# BB_DIO_Cape.net
KiCad netlist of a schematic drawn in EAGLE
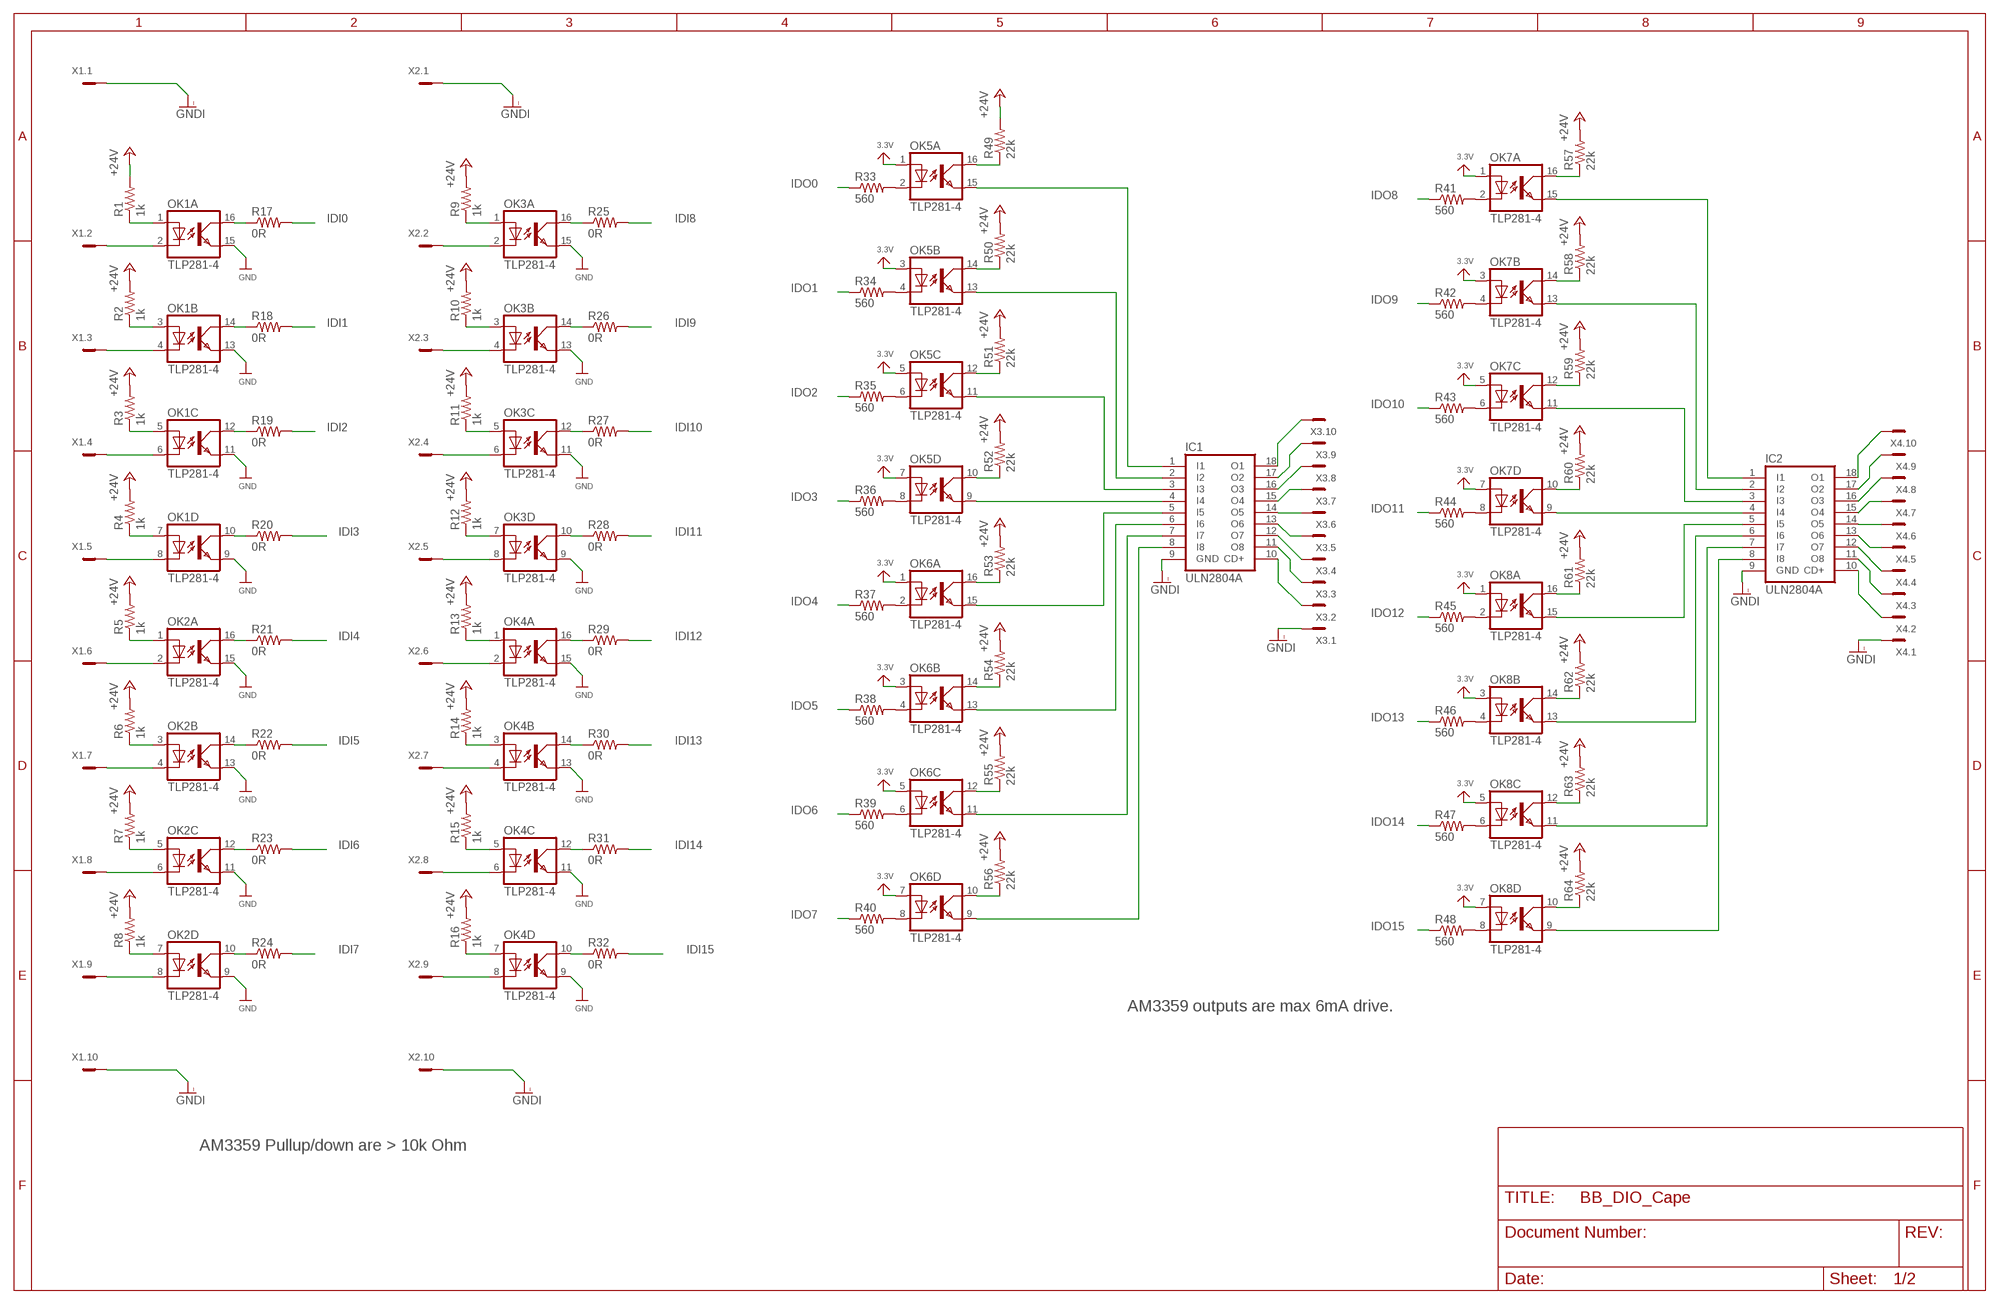
[diagram p0: schematic, sheet 1]
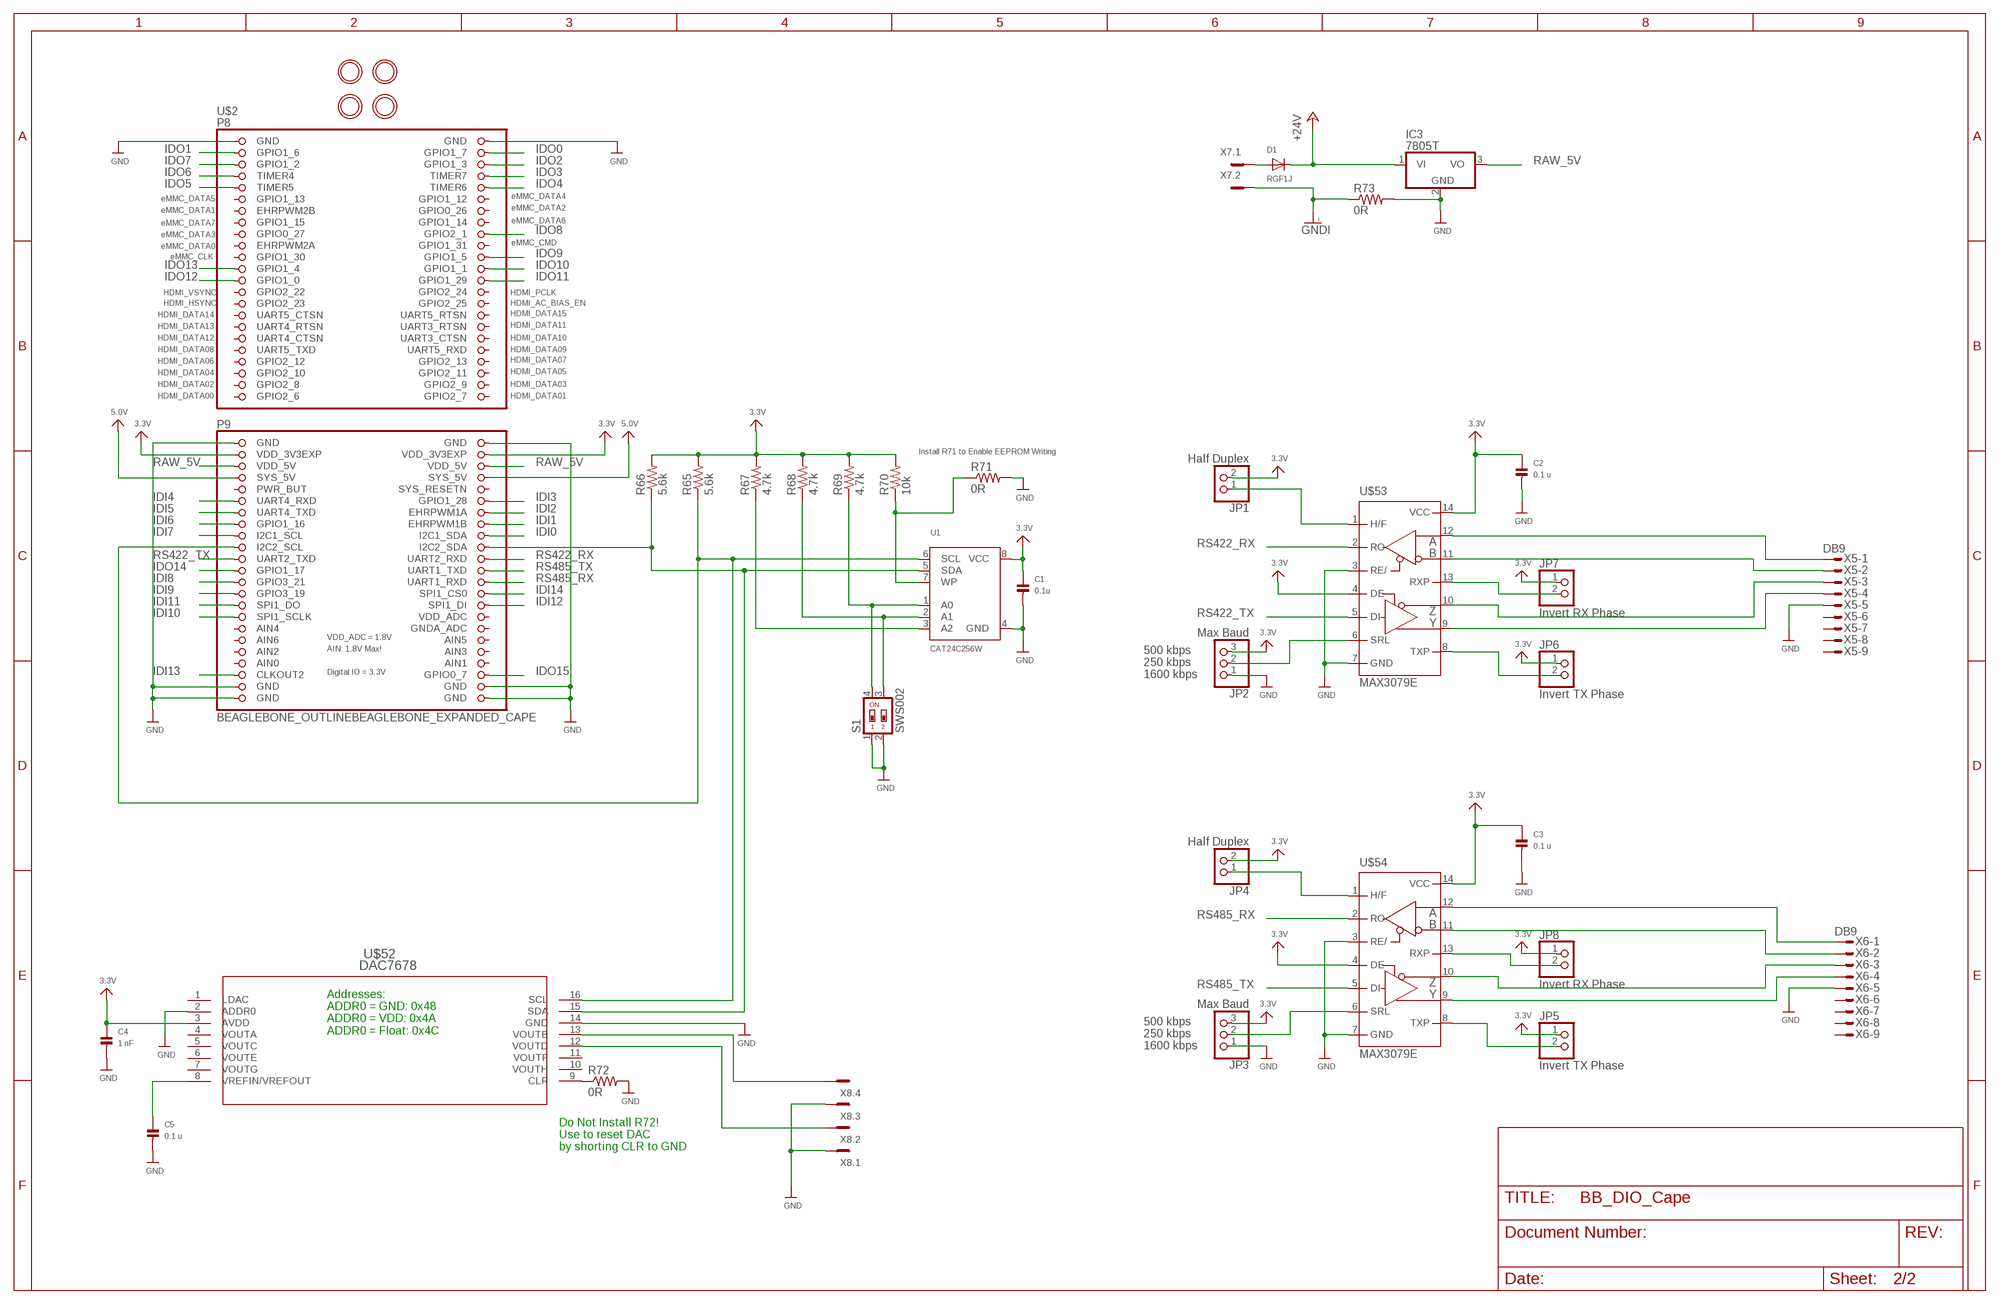
[diagram p1: schematic, sheet 2]

(export (version "E")
  (design (tool "Eeschema 10.0.6"))
  (components
    (comp (ref "IC1")
      (value "ULN2804A")
      (footprint "eagle-import:SO18W")
      (libsource (lib "eagle-import") (part "ULN2803ASOIC18"))
    )
    (comp (ref "IC2")
      (value "ULN2804A")
      (footprint "eagle-import:SO18W")
      (libsource (lib "eagle-import") (part "ULN2803ASOIC18"))
    )
    (comp (ref "OK1")
      (value "TLP281-4")
      (footprint "eagle-import:MINI-FLAT-16")
      (libsource (lib "eagle-import") (part "TLP283-4"))
    )
    (comp (ref "OK2")
      (value "TLP281-4")
      (footprint "eagle-import:MINI-FLAT-16")
      (libsource (lib "eagle-import") (part "TLP283-4"))
    )
    (comp (ref "OK3")
      (value "TLP281-4")
      (footprint "eagle-import:MINI-FLAT-16")
      (libsource (lib "eagle-import") (part "TLP283-4"))
    )
    (comp (ref "OK4")
      (value "TLP281-4")
      (footprint "eagle-import:MINI-FLAT-16")
      (libsource (lib "eagle-import") (part "TLP283-4"))
    )
    (comp (ref "OK5")
      (value "TLP281-4")
      (footprint "eagle-import:MINI-FLAT-16")
      (libsource (lib "eagle-import") (part "TLP283-4"))
    )
    (comp (ref "OK6")
      (value "TLP281-4")
      (footprint "eagle-import:MINI-FLAT-16")
      (libsource (lib "eagle-import") (part "TLP283-4"))
    )
    (comp (ref "OK7")
      (value "TLP281-4")
      (footprint "eagle-import:MINI-FLAT-16")
      (libsource (lib "eagle-import") (part "TLP283-4"))
    )
    (comp (ref "OK8")
      (value "TLP281-4")
      (footprint "eagle-import:MINI-FLAT-16")
      (libsource (lib "eagle-import") (part "TLP283-4"))
    )
    (comp (ref "R1")
      (value "1k")
      (footprint "eagle-import:R0603")
      (libsource (lib "eagle-import") (part "R-US_R0603"))
    )
    (comp (ref "R2")
      (value "1k")
      (footprint "eagle-import:R0603")
      (libsource (lib "eagle-import") (part "R-US_R0603"))
    )
    (comp (ref "R3")
      (value "1k")
      (footprint "eagle-import:R0603")
      (libsource (lib "eagle-import") (part "R-US_R0603"))
    )
    (comp (ref "R4")
      (value "1k")
      (footprint "eagle-import:R0603")
      (libsource (lib "eagle-import") (part "R-US_R0603"))
    )
    (comp (ref "R5")
      (value "1k")
      (footprint "eagle-import:R0603")
      (libsource (lib "eagle-import") (part "R-US_R0603"))
    )
    (comp (ref "R6")
      (value "1k")
      (footprint "eagle-import:R0603")
      (libsource (lib "eagle-import") (part "R-US_R0603"))
    )
    (comp (ref "R7")
      (value "1k")
      (footprint "eagle-import:R0603")
      (libsource (lib "eagle-import") (part "R-US_R0603"))
    )
    (comp (ref "R8")
      (value "1k")
      (footprint "eagle-import:R0603")
      (libsource (lib "eagle-import") (part "R-US_R0603"))
    )
    (comp (ref "R9")
      (value "1k")
      (footprint "eagle-import:R0603")
      (libsource (lib "eagle-import") (part "R-US_R0603"))
    )
    (comp (ref "R10")
      (value "1k")
      (footprint "eagle-import:R0603")
      (libsource (lib "eagle-import") (part "R-US_R0603"))
    )
    (comp (ref "R11")
      (value "1k")
      (footprint "eagle-import:R0603")
      (libsource (lib "eagle-import") (part "R-US_R0603"))
    )
    (comp (ref "R12")
      (value "1k")
      (footprint "eagle-import:R0603")
      (libsource (lib "eagle-import") (part "R-US_R0603"))
    )
    (comp (ref "R13")
      (value "1k")
      (footprint "eagle-import:R0603")
      (libsource (lib "eagle-import") (part "R-US_R0603"))
    )
    (comp (ref "R14")
      (value "1k")
      (footprint "eagle-import:R0603")
      (libsource (lib "eagle-import") (part "R-US_R0603"))
    )
    (comp (ref "R15")
      (value "1k")
      (footprint "eagle-import:R0603")
      (libsource (lib "eagle-import") (part "R-US_R0603"))
    )
    (comp (ref "R16")
      (value "1k")
      (footprint "eagle-import:R0603")
      (libsource (lib "eagle-import") (part "R-US_R0603"))
    )
    (comp (ref "R17")
      (value "0R")
      (footprint "eagle-import:R0603")
      (libsource (lib "eagle-import") (part "R-US_R0603"))
    )
    (comp (ref "R18")
      (value "0R")
      (footprint "eagle-import:R0603")
      (libsource (lib "eagle-import") (part "R-US_R0603"))
    )
    (comp (ref "R19")
      (value "0R")
      (footprint "eagle-import:R0603")
      (libsource (lib "eagle-import") (part "R-US_R0603"))
    )
    (comp (ref "R20")
      (value "0R")
      (footprint "eagle-import:R0603")
      (libsource (lib "eagle-import") (part "R-US_R0603"))
    )
    (comp (ref "R21")
      (value "0R")
      (footprint "eagle-import:R0603")
      (libsource (lib "eagle-import") (part "R-US_R0603"))
    )
    (comp (ref "R22")
      (value "0R")
      (footprint "eagle-import:R0603")
      (libsource (lib "eagle-import") (part "R-US_R0603"))
    )
    (comp (ref "R23")
      (value "0R")
      (footprint "eagle-import:R0603")
      (libsource (lib "eagle-import") (part "R-US_R0603"))
    )
    (comp (ref "R24")
      (value "0R")
      (footprint "eagle-import:R0603")
      (libsource (lib "eagle-import") (part "R-US_R0603"))
    )
    (comp (ref "R25")
      (value "0R")
      (footprint "eagle-import:R0603")
      (libsource (lib "eagle-import") (part "R-US_R0603"))
    )
    (comp (ref "R26")
      (value "0R")
      (footprint "eagle-import:R0603")
      (libsource (lib "eagle-import") (part "R-US_R0603"))
    )
    (comp (ref "R27")
      (value "0R")
      (footprint "eagle-import:R0603")
      (libsource (lib "eagle-import") (part "R-US_R0603"))
    )
    (comp (ref "R28")
      (value "0R")
      (footprint "eagle-import:R0603")
      (libsource (lib "eagle-import") (part "R-US_R0603"))
    )
    (comp (ref "R29")
      (value "0R")
      (footprint "eagle-import:R0603")
      (libsource (lib "eagle-import") (part "R-US_R0603"))
    )
    (comp (ref "R30")
      (value "0R")
      (footprint "eagle-import:R0603")
      (libsource (lib "eagle-import") (part "R-US_R0603"))
    )
    (comp (ref "R31")
      (value "0R")
      (footprint "eagle-import:R0603")
      (libsource (lib "eagle-import") (part "R-US_R0603"))
    )
    (comp (ref "R32")
      (value "0R")
      (footprint "eagle-import:R0603")
      (libsource (lib "eagle-import") (part "R-US_R0603"))
    )
    (comp (ref "R33")
      (value "560")
      (footprint "eagle-import:R0603")
      (libsource (lib "eagle-import") (part "R-US_R0603"))
    )
    (comp (ref "R34")
      (value "560")
      (footprint "eagle-import:R0603")
      (libsource (lib "eagle-import") (part "R-US_R0603"))
    )
    (comp (ref "R35")
      (value "560")
      (footprint "eagle-import:R0603")
      (libsource (lib "eagle-import") (part "R-US_R0603"))
    )
    (comp (ref "R36")
      (value "560")
      (footprint "eagle-import:R0603")
      (libsource (lib "eagle-import") (part "R-US_R0603"))
    )
    (comp (ref "R37")
      (value "560")
      (footprint "eagle-import:R0603")
      (libsource (lib "eagle-import") (part "R-US_R0603"))
    )
    (comp (ref "R38")
      (value "560")
      (footprint "eagle-import:R0603")
      (libsource (lib "eagle-import") (part "R-US_R0603"))
    )
    (comp (ref "R39")
      (value "560")
      (footprint "eagle-import:R0603")
      (libsource (lib "eagle-import") (part "R-US_R0603"))
    )
    (comp (ref "R40")
      (value "560")
      (footprint "eagle-import:R0603")
      (libsource (lib "eagle-import") (part "R-US_R0603"))
    )
    (comp (ref "R41")
      (value "560")
      (footprint "eagle-import:R0603")
      (libsource (lib "eagle-import") (part "R-US_R0603"))
    )
    (comp (ref "R42")
      (value "560")
      (footprint "eagle-import:R0603")
      (libsource (lib "eagle-import") (part "R-US_R0603"))
    )
    (comp (ref "R43")
      (value "560")
      (footprint "eagle-import:R0603")
      (libsource (lib "eagle-import") (part "R-US_R0603"))
    )
    (comp (ref "R44")
      (value "560")
      (footprint "eagle-import:R0603")
      (libsource (lib "eagle-import") (part "R-US_R0603"))
    )
    (comp (ref "R45")
      (value "560")
      (footprint "eagle-import:R0603")
      (libsource (lib "eagle-import") (part "R-US_R0603"))
    )
    (comp (ref "R46")
      (value "560")
      (footprint "eagle-import:R0603")
      (libsource (lib "eagle-import") (part "R-US_R0603"))
    )
    (comp (ref "R47")
      (value "560")
      (footprint "eagle-import:R0603")
      (libsource (lib "eagle-import") (part "R-US_R0603"))
    )
    (comp (ref "R48")
      (value "560")
      (footprint "eagle-import:R0603")
      (libsource (lib "eagle-import") (part "R-US_R0603"))
    )
    (comp (ref "R49")
      (value "22k")
      (footprint "eagle-import:R0603")
      (libsource (lib "eagle-import") (part "R-US_R0603"))
    )
    (comp (ref "R50")
      (value "22k")
      (footprint "eagle-import:R0603")
      (libsource (lib "eagle-import") (part "R-US_R0603"))
    )
    (comp (ref "R51")
      (value "22k")
      (footprint "eagle-import:R0603")
      (libsource (lib "eagle-import") (part "R-US_R0603"))
    )
    (comp (ref "R52")
      (value "22k")
      (footprint "eagle-import:R0603")
      (libsource (lib "eagle-import") (part "R-US_R0603"))
    )
    (comp (ref "R53")
      (value "22k")
      (footprint "eagle-import:R0603")
      (libsource (lib "eagle-import") (part "R-US_R0603"))
    )
    (comp (ref "R54")
      (value "22k")
      (footprint "eagle-import:R0603")
      (libsource (lib "eagle-import") (part "R-US_R0603"))
    )
    (comp (ref "R55")
      (value "22k")
      (footprint "eagle-import:R0603")
      (libsource (lib "eagle-import") (part "R-US_R0603"))
    )
    (comp (ref "R56")
      (value "22k")
      (footprint "eagle-import:R0603")
      (libsource (lib "eagle-import") (part "R-US_R0603"))
    )
    (comp (ref "R57")
      (value "22k")
      (footprint "eagle-import:R0603")
      (libsource (lib "eagle-import") (part "R-US_R0603"))
    )
    (comp (ref "R58")
      (value "22k")
      (footprint "eagle-import:R0603")
      (libsource (lib "eagle-import") (part "R-US_R0603"))
    )
    (comp (ref "R59")
      (value "22k")
      (footprint "eagle-import:R0603")
      (libsource (lib "eagle-import") (part "R-US_R0603"))
    )
    (comp (ref "R60")
      (value "22k")
      (footprint "eagle-import:R0603")
      (libsource (lib "eagle-import") (part "R-US_R0603"))
    )
    (comp (ref "R61")
      (value "22k")
      (footprint "eagle-import:R0603")
      (libsource (lib "eagle-import") (part "R-US_R0603"))
    )
    (comp (ref "R62")
      (value "22k")
      (footprint "eagle-import:R0603")
      (libsource (lib "eagle-import") (part "R-US_R0603"))
    )
    (comp (ref "R63")
      (value "22k")
      (footprint "eagle-import:R0603")
      (libsource (lib "eagle-import") (part "R-US_R0603"))
    )
    (comp (ref "R64")
      (value "22k")
      (footprint "eagle-import:R0603")
      (libsource (lib "eagle-import") (part "R-US_R0603"))
    )
    (comp (ref "X1")
      (value "MC10")
      (footprint "eagle-import:MC10")
      (libsource (lib "eagle-import") (part "MC10"))
    )
    (comp (ref "X2")
      (value "MC10")
      (footprint "eagle-import:MC10")
      (libsource (lib "eagle-import") (part "MC10"))
    )
    (comp (ref "X3")
      (value "MC10")
      (footprint "eagle-import:MC10")
      (libsource (lib "eagle-import") (part "MC10"))
    )
    (comp (ref "X4")
      (value "MC10")
      (footprint "eagle-import:MC10")
      (libsource (lib "eagle-import") (part "MC10"))
    )
    (comp (ref "C1")
      (value "0.1u")
      (footprint "eagle-import:_0603")
      (libsource (lib "eagle-import") (part "CAP_CERAMIC_0603"))
    )
    (comp (ref "C2")
      (value "0.1 u")
      (footprint "eagle-import:0603")
      (libsource (lib "eagle-import") (part "CAP_CERAMIC0603"))
    )
    (comp (ref "C3")
      (value "0.1 u")
      (footprint "eagle-import:0603")
      (libsource (lib "eagle-import") (part "CAP_CERAMIC0603"))
    )
    (comp (ref "C4")
      (value "1 nF")
      (footprint "eagle-import:0603")
      (libsource (lib "eagle-import") (part "CAP_CERAMIC0603"))
    )
    (comp (ref "C5")
      (value "0.1 u")
      (footprint "eagle-import:0603")
      (libsource (lib "eagle-import") (part "CAP_CERAMIC0603"))
    )
    (comp (ref "D1")
      (value "RGF1J")
      (footprint "eagle-import:SMADIODE")
      (libsource (lib "eagle-import") (part "DIODESMA"))
    )
    (comp (ref "IC3")
      (value "7805T")
      (footprint "eagle-import:TO220H")
      (libsource (lib "eagle-import") (part "78T05"))
    )
    (comp (ref "JP1")
      (value "Half Duplex")
      (footprint "eagle-import:1X02_ROUND")
      (libsource (lib "eagle-import") (part "HEADER-1X2ROUND"))
    )
    (comp (ref "JP2")
      (value "Max Baud")
      (footprint "eagle-import:1X03_ROUND")
      (libsource (lib "eagle-import") (part "HEADER-1X3ROUND"))
    )
    (comp (ref "JP3")
      (value "Max Baud")
      (footprint "eagle-import:1X03_ROUND")
      (libsource (lib "eagle-import") (part "HEADER-1X3ROUND"))
    )
    (comp (ref "JP4")
      (value "Half Duplex")
      (footprint "eagle-import:1X02_ROUND")
      (libsource (lib "eagle-import") (part "HEADER-1X2ROUND"))
    )
    (comp (ref "JP5")
      (value "Invert TX Phase")
      (footprint "eagle-import:1X02_ROUND")
      (libsource (lib "eagle-import") (part "HEADER-1X2ROUND"))
    )
    (comp (ref "JP6")
      (value "Invert TX Phase")
      (footprint "eagle-import:1X02_ROUND")
      (libsource (lib "eagle-import") (part "HEADER-1X2ROUND"))
    )
    (comp (ref "JP7")
      (value "Invert RX Phase")
      (footprint "eagle-import:1X02_ROUND")
      (libsource (lib "eagle-import") (part "HEADER-1X2ROUND"))
    )
    (comp (ref "JP8")
      (value "Invert RX Phase")
      (footprint "eagle-import:1X02_ROUND")
      (libsource (lib "eagle-import") (part "HEADER-1X2ROUND"))
    )
    (comp (ref "R65")
      (value "5.6k")
      (footprint "eagle-import:R0603")
      (libsource (lib "eagle-import") (part "R-US_R0603"))
    )
    (comp (ref "R66")
      (value "5.6k")
      (footprint "eagle-import:R0603")
      (libsource (lib "eagle-import") (part "R-US_R0603"))
    )
    (comp (ref "R67")
      (value "4.7k")
      (footprint "eagle-import:R0603")
      (libsource (lib "eagle-import") (part "R-US_R0603"))
    )
    (comp (ref "R68")
      (value "4.7k")
      (footprint "eagle-import:R0603")
      (libsource (lib "eagle-import") (part "R-US_R0603"))
    )
    (comp (ref "R69")
      (value "4.7k")
      (footprint "eagle-import:R0603")
      (libsource (lib "eagle-import") (part "R-US_R0603"))
    )
    (comp (ref "R70")
      (value "10k")
      (footprint "eagle-import:R0603")
      (libsource (lib "eagle-import") (part "R-US_R0603"))
    )
    (comp (ref "R71")
      (value "0R")
      (footprint "eagle-import:R0603")
      (libsource (lib "eagle-import") (part "R-US_R0603"))
    )
    (comp (ref "R72")
      (value "0R")
      (footprint "eagle-import:R0603")
      (libsource (lib "eagle-import") (part "R-US_R0603"))
    )
    (comp (ref "R73")
      (value "0R")
      (footprint "eagle-import:M1206")
      (libsource (lib "eagle-import") (part "R-US_M1206"))
    )
    (comp (ref "S1")
      (value "SWS002")
      (footprint "eagle-import:SMS-002")
      (libsource (lib "eagle-import") (part "SWS002"))
    )
    (comp (ref "U$2")
      (value "BEAGLEBONE_OUTLINEBEAGLEBONE_EXPANDED_CAPE")
      (footprint "eagle-import:BEAGLEBONE_SHIELD")
      (libsource (lib "eagle-import") (part "BEAGLEBONE_OUTLINEBEAGLEBONE_EXPANDED_CAPE"))
    )
    (comp (ref "U$22")
      (value "MOUNTINGHOLE3.0THIN")
      (footprint "eagle-import:MOUNTINGHOLE_3.0_PLATEDTHIN")
      (libsource (lib "eagle-import") (part "MOUNTINGHOLE3.0THIN"))
    )
    (comp (ref "U$23")
      (value "MOUNTINGHOLE3.0THIN")
      (footprint "eagle-import:MOUNTINGHOLE_3.0_PLATEDTHIN")
      (libsource (lib "eagle-import") (part "MOUNTINGHOLE3.0THIN"))
    )
    (comp (ref "U$52")
      (value "DAC7678")
      (footprint "eagle-import:PW16")
      (libsource (lib "eagle-import") (part "DAC7678"))
    )
    (comp (ref "U$53")
      (value "MAX3079E")
      (footprint "eagle-import:SO14")
      (libsource (lib "eagle-import") (part "MAX3079E"))
    )
    (comp (ref "U$54")
      (value "MAX3079E")
      (footprint "eagle-import:SO14")
      (libsource (lib "eagle-import") (part "MAX3079E"))
    )
    (comp (ref "U$71")
      (value "MOUNTINGHOLE3.0THIN")
      (footprint "eagle-import:MOUNTINGHOLE_3.0_PLATEDTHIN")
      (libsource (lib "eagle-import") (part "MOUNTINGHOLE3.0THIN"))
    )
    (comp (ref "U$72")
      (value "MOUNTINGHOLE3.0THIN")
      (footprint "eagle-import:MOUNTINGHOLE_3.0_PLATEDTHIN")
      (libsource (lib "eagle-import") (part "MOUNTINGHOLE3.0THIN"))
    )
    (comp (ref "U1")
      (value "CAT24C256W")
      (footprint "eagle-import:SOIC8_150MIL")
      (libsource (lib "eagle-import") (part "EEPROM_I2C_SOIC8_GENERIC"))
    )
    (comp (ref "X5")
      (value "DB9")
      (footprint "eagle-import:182-009-MALE")
      (libsource (lib "eagle-import") (part "M09?S-182"))
    )
    (comp (ref "X6")
      (value "DB9")
      (footprint "eagle-import:182-009-MALE")
      (libsource (lib "eagle-import") (part "M09?S-182"))
    )
    (comp (ref "X7")
      (value "MC2")
      (footprint "eagle-import:MC2")
      (libsource (lib "eagle-import") (part "MC2"))
    )
    (comp (ref "X8")
      (value "MC4")
      (footprint "eagle-import:MC4")
      (libsource (lib "eagle-import") (part "MC4"))
    )
  )
  (nets
    (net (code "1") (name "+24V") (class "Default")
      (node (ref "D1") (pin "C") (pinfunction "C_C") (pintype "passive"))
      (node (ref "IC3") (pin "1") (pinfunction "VI_1") (pintype "input"))
      (node (ref "R1") (pin "2") (pinfunction "2_2") (pintype "passive"))
      (node (ref "R10") (pin "2") (pinfunction "2_2") (pintype "passive"))
      (node (ref "R11") (pin "2") (pinfunction "2_2") (pintype "passive"))
      (node (ref "R12") (pin "2") (pinfunction "2_2") (pintype "passive"))
      (node (ref "R13") (pin "2") (pinfunction "2_2") (pintype "passive"))
      (node (ref "R14") (pin "2") (pinfunction "2_2") (pintype "passive"))
      (node (ref "R15") (pin "2") (pinfunction "2_2") (pintype "passive"))
      (node (ref "R16") (pin "2") (pinfunction "2_2") (pintype "passive"))
      (node (ref "R2") (pin "2") (pinfunction "2_2") (pintype "passive"))
      (node (ref "R3") (pin "2") (pinfunction "2_2") (pintype "passive"))
      (node (ref "R4") (pin "2") (pinfunction "2_2") (pintype "passive"))
      (node (ref "R49") (pin "2") (pinfunction "2_2") (pintype "passive"))
      (node (ref "R5") (pin "2") (pinfunction "2_2") (pintype "passive"))
      (node (ref "R50") (pin "2") (pinfunction "2_2") (pintype "passive"))
      (node (ref "R51") (pin "2") (pinfunction "2_2") (pintype "passive"))
      (node (ref "R52") (pin "2") (pinfunction "2_2") (pintype "passive"))
      (node (ref "R53") (pin "2") (pinfunction "2_2") (pintype "passive"))
      (node (ref "R54") (pin "2") (pinfunction "2_2") (pintype "passive"))
      (node (ref "R55") (pin "2") (pinfunction "2_2") (pintype "passive"))
      (node (ref "R56") (pin "2") (pinfunction "2_2") (pintype "passive"))
      (node (ref "R57") (pin "2") (pinfunction "2_2") (pintype "passive"))
      (node (ref "R58") (pin "2") (pinfunction "2_2") (pintype "passive"))
      (node (ref "R59") (pin "2") (pinfunction "2_2") (pintype "passive"))
      (node (ref "R6") (pin "2") (pinfunction "2_2") (pintype "passive"))
      (node (ref "R60") (pin "2") (pinfunction "2_2") (pintype "passive"))
      (node (ref "R61") (pin "2") (pinfunction "2_2") (pintype "passive"))
      (node (ref "R62") (pin "2") (pinfunction "2_2") (pintype "passive"))
      (node (ref "R63") (pin "2") (pinfunction "2_2") (pintype "passive"))
      (node (ref "R64") (pin "2") (pinfunction "2_2") (pintype "passive"))
      (node (ref "R7") (pin "2") (pinfunction "2_2") (pintype "passive"))
      (node (ref "R8") (pin "2") (pinfunction "2_2") (pintype "passive"))
      (node (ref "R9") (pin "2") (pinfunction "2_2") (pintype "passive"))
    )
    (net (code "2") (name "3.3V") (class "Default")
      (node (ref "C1") (pin "1") (pinfunction "P$1_1") (pintype "passive"))
      (node (ref "C2") (pin "1") (pinfunction "P$1_1") (pintype "passive"))
      (node (ref "C3") (pin "1") (pinfunction "P$1_1") (pintype "passive"))
      (node (ref "C4") (pin "1") (pinfunction "P$1_1") (pintype "passive"))
      (node (ref "JP1") (pin "2") (pinfunction "2_2") (pintype "passive"))
      (node (ref "JP2") (pin "3") (pinfunction "3_3") (pintype "passive"))
      (node (ref "JP3") (pin "3") (pinfunction "3_3") (pintype "passive"))
      (node (ref "JP4") (pin "2") (pinfunction "2_2") (pintype "passive"))
      (node (ref "JP5") (pin "1") (pinfunction "1_1") (pintype "passive"))
      (node (ref "JP6") (pin "1") (pinfunction "1_1") (pintype "passive"))
      (node (ref "JP7") (pin "1") (pinfunction "1_1") (pintype "passive"))
      (node (ref "JP8") (pin "1") (pinfunction "1_1") (pintype "passive"))
      (node (ref "OK5") (pin "1") (pinfunction "A_1") (pintype "passive"))
      (node (ref "OK5") (pin "3") (pinfunction "A_3") (pintype "passive"))
      (node (ref "OK5") (pin "5") (pinfunction "A_5") (pintype "passive"))
      (node (ref "OK5") (pin "7") (pinfunction "A_7") (pintype "passive"))
      (node (ref "OK6") (pin "1") (pinfunction "A_1") (pintype "passive"))
      (node (ref "OK6") (pin "3") (pinfunction "A_3") (pintype "passive"))
      (node (ref "OK6") (pin "5") (pinfunction "A_5") (pintype "passive"))
      (node (ref "OK6") (pin "7") (pinfunction "A_7") (pintype "passive"))
      (node (ref "OK7") (pin "1") (pinfunction "A_1") (pintype "passive"))
      (node (ref "OK7") (pin "3") (pinfunction "A_3") (pintype "passive"))
      (node (ref "OK7") (pin "5") (pinfunction "A_5") (pintype "passive"))
      (node (ref "OK7") (pin "7") (pinfunction "A_7") (pintype "passive"))
      (node (ref "OK8") (pin "1") (pinfunction "A_1") (pintype "passive"))
      (node (ref "OK8") (pin "3") (pinfunction "A_3") (pintype "passive"))
      (node (ref "OK8") (pin "5") (pinfunction "A_5") (pintype "passive"))
      (node (ref "OK8") (pin "7") (pinfunction "A_7") (pintype "passive"))
      (node (ref "R65") (pin "2") (pinfunction "2_2") (pintype "passive"))
      (node (ref "R66") (pin "2") (pinfunction "2_2") (pintype "passive"))
      (node (ref "R67") (pin "2") (pinfunction "2_2") (pintype "passive"))
      (node (ref "R68") (pin "2") (pinfunction "2_2") (pintype "passive"))
      (node (ref "R69") (pin "2") (pinfunction "2_2") (pintype "passive"))
      (node (ref "R70") (pin "2") (pinfunction "2_2") (pintype "passive"))
      (node (ref "U$2") (pin "49") (pinfunction "VDD_3V3EXP_49") (pintype "power_in"))
      (node (ref "U$2") (pin "50") (pinfunction "VDD_3V3EXP_50") (pintype "power_in"))
      (node (ref "U$52") (pin "3") (pinfunction "AVDD_3") (pintype "power_in"))
      (node (ref "U$53") (pin "14") (pinfunction "VCC_14") (pintype "input"))
      (node (ref "U$53") (pin "4") (pinfunction "DE_4") (pintype "input"))
      (node (ref "U$54") (pin "14") (pinfunction "VCC_14") (pintype "input"))
      (node (ref "U$54") (pin "4") (pinfunction "DE_4") (pintype "input"))
      (node (ref "U1") (pin "8") (pinfunction "VCC_8") (pintype "power_in"))
    )
    (net (code "3") (name "5.0V") (class "Default")
      (node (ref "U$2") (pin "53") (pinfunction "SYS_5V_53") (pintype "power_in"))
      (node (ref "U$2") (pin "54") (pinfunction "SYS_5V_54") (pintype "power_in"))
    )
    (net (code "4") (name "GND") (class "Default")
      (node (ref "C1") (pin "2") (pinfunction "P$2_2") (pintype "passive"))
      (node (ref "C2") (pin "2") (pinfunction "P$2_2") (pintype "passive"))
      (node (ref "C3") (pin "2") (pinfunction "P$2_2") (pintype "passive"))
      (node (ref "C4") (pin "2") (pinfunction "P$2_2") (pintype "passive"))
      (node (ref "C5") (pin "2") (pinfunction "P$2_2") (pintype "passive"))
      (node (ref "IC3") (pin "2") (pinfunction "GND_2") (pintype "passive"))
      (node (ref "JP2") (pin "1") (pinfunction "1_1") (pintype "passive"))
      (node (ref "JP3") (pin "1") (pinfunction "1_1") (pintype "passive"))
      (node (ref "OK1") (pin "11") (pinfunction "EMIT_11") (pintype "passive"))
      (node (ref "OK1") (pin "13") (pinfunction "EMIT_13") (pintype "passive"))
      (node (ref "OK1") (pin "15") (pinfunction "EMIT_15") (pintype "passive"))
      (node (ref "OK1") (pin "9") (pinfunction "EMIT_9") (pintype "passive"))
      (node (ref "OK2") (pin "11") (pinfunction "EMIT_11") (pintype "passive"))
      (node (ref "OK2") (pin "13") (pinfunction "EMIT_13") (pintype "passive"))
      (node (ref "OK2") (pin "15") (pinfunction "EMIT_15") (pintype "passive"))
      (node (ref "OK2") (pin "9") (pinfunction "EMIT_9") (pintype "passive"))
      (node (ref "OK3") (pin "11") (pinfunction "EMIT_11") (pintype "passive"))
      (node (ref "OK3") (pin "13") (pinfunction "EMIT_13") (pintype "passive"))
      (node (ref "OK3") (pin "15") (pinfunction "EMIT_15") (pintype "passive"))
      (node (ref "OK3") (pin "9") (pinfunction "EMIT_9") (pintype "passive"))
      (node (ref "OK4") (pin "11") (pinfunction "EMIT_11") (pintype "passive"))
      (node (ref "OK4") (pin "13") (pinfunction "EMIT_13") (pintype "passive"))
      (node (ref "OK4") (pin "15") (pinfunction "EMIT_15") (pintype "passive"))
      (node (ref "OK4") (pin "9") (pinfunction "EMIT_9") (pintype "passive"))
      (node (ref "R71") (pin "2") (pinfunction "2_2") (pintype "passive"))
      (node (ref "R72") (pin "2") (pinfunction "2_2") (pintype "passive"))
      (node (ref "R73") (pin "2") (pinfunction "2_2") (pintype "passive"))
      (node (ref "S1") (pin "1") (pinfunction "1_1") (pintype "passive"))
      (node (ref "S1") (pin "2") (pinfunction "2_2") (pintype "passive"))
      (node (ref "U$2") (pin "1") (pinfunction "GND_1") (pintype "power_in"))
      (node (ref "U$2") (pin "2") (pinfunction "GND_2") (pintype "power_in"))
      (node (ref "U$2") (pin "47") (pinfunction "GND_47") (pintype "power_in"))
      (node (ref "U$2") (pin "48") (pinfunction "GND_48") (pintype "power_in"))
      (node (ref "U$2") (pin "89") (pinfunction "GND_89") (pintype "power_in"))
      (node (ref "U$2") (pin "90") (pinfunction "GND_90") (pintype "power_in"))
      (node (ref "U$2") (pin "91") (pinfunction "GND_91") (pintype "power_in"))
      (node (ref "U$2") (pin "92") (pinfunction "GND_92") (pintype "power_in"))
      (node (ref "U$52") (pin "14") (pinfunction "GND_14") (pintype "power_in"))
      (node (ref "U$52") (pin "2") (pinfunction "ADDR0_2") (pintype "input"))
      (node (ref "U$53") (pin "3") (pinfunction "RE/_3") (pintype "input"))
      (node (ref "U$53") (pin "7") (pinfunction "GND_7") (pintype "input"))
      (node (ref "U$54") (pin "3") (pinfunction "RE/_3") (pintype "input"))
      (node (ref "U$54") (pin "7") (pinfunction "GND_7") (pintype "input"))
      (node (ref "U1") (pin "4") (pinfunction "GND_4") (pintype "power_in"))
      (node (ref "X5") (pin "5") (pinfunction "M_5") (pintype "passive"))
      (node (ref "X6") (pin "5") (pinfunction "M_5") (pintype "passive"))
      (node (ref "X8") (pin "1") (pinfunction "SK_1") (pintype "passive"))
      (node (ref "X8") (pin "3") (pinfunction "SK_3") (pintype "passive"))
    )
    (net (code "5") (name "GNDA_ADC") (class "Default")
      (node (ref "U$2") (pin "80") (pinfunction "GNDA_ADC_80") (pintype "power_in"))
    )
    (net (code "6") (name "GNDI") (class "Default")
      (node (ref "IC1") (pin "9") (pinfunction "GND_9") (pintype "power_in"))
      (node (ref "IC2") (pin "9") (pinfunction "GND_9") (pintype "power_in"))
      (node (ref "R73") (pin "1") (pinfunction "1_1") (pintype "passive"))
      (node (ref "X1") (pin "1") (pinfunction "SK_1") (pintype "passive"))
      (node (ref "X1") (pin "10") (pinfunction "SK_10") (pintype "passive"))
      (node (ref "X2") (pin "1") (pinfunction "SK_1") (pintype "passive"))
      (node (ref "X2") (pin "10") (pinfunction "SK_10") (pintype "passive"))
      (node (ref "X3") (pin "1") (pinfunction "SK_1") (pintype "passive"))
      (node (ref "X4") (pin "1") (pinfunction "SK_1") (pintype "passive"))
      (node (ref "X7") (pin "2") (pinfunction "SK_2") (pintype "passive"))
    )
    (net (code "7") (name "IDI0") (class "Default")
      (node (ref "R17") (pin "2") (pinfunction "2_2") (pintype "passive"))
      (node (ref "U$2") (pin "64") (pinfunction "I2C1_SDA_64") (pintype "bidirectional"))
    )
    (net (code "8") (name "IDI1") (class "Default")
      (node (ref "R18") (pin "2") (pinfunction "2_2") (pintype "passive"))
      (node (ref "U$2") (pin "62") (pinfunction "EHRPWM1B_62") (pintype "bidirectional"))
    )
    (net (code "9") (name "IDI2") (class "Default")
      (node (ref "R19") (pin "2") (pinfunction "2_2") (pintype "passive"))
      (node (ref "U$2") (pin "60") (pinfunction "EHRPWM1A_60") (pintype "bidirectional"))
    )
    (net (code "10") (name "IDI3") (class "Default")
      (node (ref "R20") (pin "2") (pinfunction "2_2") (pintype "passive"))
      (node (ref "U$2") (pin "58") (pinfunction "GPIO1_28_58") (pintype "bidirectional"))
    )
    (net (code "11") (name "IDI4") (class "Default")
      (node (ref "R21") (pin "2") (pinfunction "2_2") (pintype "passive"))
      (node (ref "U$2") (pin "57") (pinfunction "UART4_RXD_57") (pintype "input"))
    )
    (net (code "12") (name "IDI5") (class "Default")
      (node (ref "R22") (pin "2") (pinfunction "2_2") (pintype "passive"))
      (node (ref "U$2") (pin "59") (pinfunction "UART4_TXD_59") (pintype "output"))
    )
    (net (code "13") (name "IDI6") (class "Default")
      (node (ref "R23") (pin "2") (pinfunction "2_2") (pintype "passive"))
      (node (ref "U$2") (pin "61") (pinfunction "GPIO1_16_61") (pintype "bidirectional"))
    )
    (net (code "14") (name "IDI7") (class "Default")
      (node (ref "R24") (pin "2") (pinfunction "2_2") (pintype "passive"))
      (node (ref "U$2") (pin "63") (pinfunction "I2C1_SCL_63") (pintype "bidirectional"))
    )
    (net (code "15") (name "IDI8") (class "Default")
      (node (ref "R25") (pin "2") (pinfunction "2_2") (pintype "passive"))
      (node (ref "U$2") (pin "71") (pinfunction "GPIO3_21_71") (pintype "bidirectional"))
    )
    (net (code "16") (name "IDI9") (class "Default")
      (node (ref "R26") (pin "2") (pinfunction "2_2") (pintype "passive"))
      (node (ref "U$2") (pin "73") (pinfunction "GPIO3_19_73") (pintype "bidirectional"))
    )
    (net (code "17") (name "IDI10") (class "Default")
      (node (ref "R27") (pin "2") (pinfunction "2_2") (pintype "passive"))
      (node (ref "U$2") (pin "77") (pinfunction "SPI1_SCLK_77") (pintype "bidirectional"))
    )
    (net (code "18") (name "IDI11") (class "Default")
      (node (ref "R28") (pin "2") (pinfunction "2_2") (pintype "passive"))
      (node (ref "U$2") (pin "75") (pinfunction "SPI1_DO_75") (pintype "bidirectional"))
    )
    (net (code "19") (name "IDI12") (class "Default")
      (node (ref "R29") (pin "2") (pinfunction "2_2") (pintype "passive"))
      (node (ref "U$2") (pin "76") (pinfunction "SPI1_DI_76") (pintype "bidirectional"))
    )
    (net (code "20") (name "IDI13") (class "Default")
      (node (ref "R30") (pin "2") (pinfunction "2_2") (pintype "passive"))
      (node (ref "U$2") (pin "87") (pinfunction "CLKOUT2_87") (pintype "output"))
    )
    (net (code "21") (name "IDI14") (class "Default")
      (node (ref "R31") (pin "2") (pinfunction "2_2") (pintype "passive"))
      (node (ref "U$2") (pin "74") (pinfunction "SPI1_CS0_74") (pintype "bidirectional"))
    )
    (net (code "22") (name "IDI15") (class "Default")
      (node (ref "R32") (pin "2") (pinfunction "2_2") (pintype "passive"))
    )
    (net (code "23") (name "IDO0") (class "Default")
      (node (ref "R33") (pin "1") (pinfunction "1_1") (pintype "passive"))
      (node (ref "U$2") (pin "4") (pinfunction "GPIO1_7_4") (pintype "bidirectional"))
    )
    (net (code "24") (name "IDO1") (class "Default")
      (node (ref "R34") (pin "1") (pinfunction "1_1") (pintype "passive"))
      (node (ref "U$2") (pin "3") (pinfunction "GPIO1_6_3") (pintype "bidirectional"))
    )
    (net (code "25") (name "IDO2") (class "Default")
      (node (ref "R35") (pin "1") (pinfunction "1_1") (pintype "passive"))
      (node (ref "U$2") (pin "6") (pinfunction "GPIO1_3_6") (pintype "bidirectional"))
    )
    (net (code "26") (name "IDO3") (class "Default")
      (node (ref "R36") (pin "1") (pinfunction "1_1") (pintype "passive"))
      (node (ref "U$2") (pin "8") (pinfunction "TIMER7_8") (pintype "bidirectional"))
    )
    (net (code "27") (name "IDO4") (class "Default")
      (node (ref "R37") (pin "1") (pinfunction "1_1") (pintype "passive"))
      (node (ref "U$2") (pin "10") (pinfunction "TIMER6_10") (pintype "bidirectional"))
    )
    (net (code "28") (name "IDO5") (class "Default")
      (node (ref "R38") (pin "1") (pinfunction "1_1") (pintype "passive"))
      (node (ref "U$2") (pin "9") (pinfunction "TIMER5_9") (pintype "bidirectional"))
    )
    (net (code "29") (name "IDO6") (class "Default")
      (node (ref "R39") (pin "1") (pinfunction "1_1") (pintype "passive"))
      (node (ref "U$2") (pin "7") (pinfunction "TIMER4_7") (pintype "bidirectional"))
    )
    (net (code "30") (name "IDO7") (class "Default")
      (node (ref "R40") (pin "1") (pinfunction "1_1") (pintype "passive"))
      (node (ref "U$2") (pin "5") (pinfunction "GPIO1_2_5") (pintype "bidirectional"))
    )
    (net (code "31") (name "IDO8") (class "Default")
      (node (ref "R41") (pin "1") (pinfunction "1_1") (pintype "passive"))
      (node (ref "U$2") (pin "18") (pinfunction "GPIO2_1_18") (pintype "bidirectional"))
    )
    (net (code "32") (name "IDO9") (class "Default")
      (node (ref "R42") (pin "1") (pinfunction "1_1") (pintype "passive"))
      (node (ref "U$2") (pin "22") (pinfunction "GPIO1_5_22") (pintype "bidirectional"))
    )
    (net (code "33") (name "IDO10") (class "Default")
      (node (ref "R43") (pin "1") (pinfunction "1_1") (pintype "passive"))
      (node (ref "U$2") (pin "24") (pinfunction "GPIO1_1_24") (pintype "bidirectional"))
    )
    (net (code "34") (name "IDO11") (class "Default")
      (node (ref "R44") (pin "1") (pinfunction "1_1") (pintype "passive"))
      (node (ref "U$2") (pin "26") (pinfunction "GPIO1_29_26") (pintype "bidirectional"))
    )
    (net (code "35") (name "IDO12") (class "Default")
      (node (ref "R45") (pin "1") (pinfunction "1_1") (pintype "passive"))
      (node (ref "U$2") (pin "25") (pinfunction "GPIO1_0_25") (pintype "bidirectional"))
    )
    (net (code "36") (name "IDO13") (class "Default")
      (node (ref "R46") (pin "1") (pinfunction "1_1") (pintype "passive"))
      (node (ref "U$2") (pin "23") (pinfunction "GPIO1_4_23") (pintype "bidirectional"))
    )
    (net (code "37") (name "IDO14") (class "Default")
      (node (ref "R47") (pin "1") (pinfunction "1_1") (pintype "passive"))
      (node (ref "U$2") (pin "69") (pinfunction "GPIO1_17_69") (pintype "bidirectional"))
    )
    (net (code "38") (name "IDO15") (class "Default")
      (node (ref "R48") (pin "1") (pinfunction "1_1") (pintype "passive"))
      (node (ref "U$2") (pin "88") (pinfunction "GPIO0_7_88") (pintype "bidirectional"))
    )
    (net (code "39") (name "Net-(C5-P$1)") (class "Default")
      (node (ref "C5") (pin "1") (pinfunction "P$1_1") (pintype "passive"))
      (node (ref "U$52") (pin "8") (pinfunction "VREFIN/VREFOUT_8") (pintype "bidirectional"))
    )
    (net (code "40") (name "Net-(IC1-CD+)") (class "Default")
      (node (ref "IC1") (pin "10") (pinfunction "CD+_10") (pintype "passive"))
      (node (ref "X3") (pin "2") (pinfunction "SK_2") (pintype "passive"))
    )
    (net (code "41") (name "Net-(IC1-I1)") (class "Default")
      (node (ref "IC1") (pin "1") (pinfunction "I1_1") (pintype "input"))
      (node (ref "OK5") (pin "15") (pinfunction "EMIT_15") (pintype "passive"))
    )
    (net (code "42") (name "Net-(IC1-I2)") (class "Default")
      (node (ref "IC1") (pin "2") (pinfunction "I2_2") (pintype "input"))
      (node (ref "OK5") (pin "13") (pinfunction "EMIT_13") (pintype "passive"))
    )
    (net (code "43") (name "Net-(IC1-I3)") (class "Default")
      (node (ref "IC1") (pin "3") (pinfunction "I3_3") (pintype "input"))
      (node (ref "OK5") (pin "11") (pinfunction "EMIT_11") (pintype "passive"))
    )
    (net (code "44") (name "Net-(IC1-I4)") (class "Default")
      (node (ref "IC1") (pin "4") (pinfunction "I4_4") (pintype "input"))
      (node (ref "OK5") (pin "9") (pinfunction "EMIT_9") (pintype "passive"))
    )
    (net (code "45") (name "Net-(IC1-I5)") (class "Default")
      (node (ref "IC1") (pin "5") (pinfunction "I5_5") (pintype "input"))
      (node (ref "OK6") (pin "15") (pinfunction "EMIT_15") (pintype "passive"))
    )
    (net (code "46") (name "Net-(IC1-I6)") (class "Default")
      (node (ref "IC1") (pin "6") (pinfunction "I6_6") (pintype "input"))
      (node (ref "OK6") (pin "13") (pinfunction "EMIT_13") (pintype "passive"))
    )
    (net (code "47") (name "Net-(IC1-I7)") (class "Default")
      (node (ref "IC1") (pin "7") (pinfunction "I7_7") (pintype "input"))
      (node (ref "OK6") (pin "11") (pinfunction "EMIT_11") (pintype "passive"))
    )
    (net (code "48") (name "Net-(IC1-I8)") (class "Default")
      (node (ref "IC1") (pin "8") (pinfunction "I8_8") (pintype "input"))
      (node (ref "OK6") (pin "9") (pinfunction "EMIT_9") (pintype "passive"))
    )
    (net (code "49") (name "Net-(IC1-O1)") (class "Default")
      (node (ref "IC1") (pin "18") (pinfunction "O1_18") (pintype "open_collector"))
      (node (ref "X3") (pin "10") (pinfunction "SK_10") (pintype "passive"))
    )
    (net (code "50") (name "Net-(IC1-O2)") (class "Default")
      (node (ref "IC1") (pin "17") (pinfunction "O2_17") (pintype "open_collector"))
      (node (ref "X3") (pin "9") (pinfunction "SK_9") (pintype "passive"))
    )
    (net (code "51") (name "Net-(IC1-O3)") (class "Default")
      (node (ref "IC1") (pin "16") (pinfunction "O3_16") (pintype "open_collector"))
      (node (ref "X3") (pin "8") (pinfunction "SK_8") (pintype "passive"))
    )
    (net (code "52") (name "Net-(IC1-O4)") (class "Default")
      (node (ref "IC1") (pin "15") (pinfunction "O4_15") (pintype "open_collector"))
      (node (ref "X3") (pin "7") (pinfunction "SK_7") (pintype "passive"))
    )
    (net (code "53") (name "Net-(IC1-O5)") (class "Default")
      (node (ref "IC1") (pin "14") (pinfunction "O5_14") (pintype "open_collector"))
      (node (ref "X3") (pin "6") (pinfunction "SK_6") (pintype "passive"))
    )
    (net (code "54") (name "Net-(IC1-O6)") (class "Default")
      (node (ref "IC1") (pin "13") (pinfunction "O6_13") (pintype "open_collector"))
      (node (ref "X3") (pin "5") (pinfunction "SK_5") (pintype "passive"))
    )
    (net (code "55") (name "Net-(IC1-O7)") (class "Default")
      (node (ref "IC1") (pin "12") (pinfunction "O7_12") (pintype "open_collector"))
      (node (ref "X3") (pin "4") (pinfunction "SK_4") (pintype "passive"))
    )
    (net (code "56") (name "Net-(IC1-O8)") (class "Default")
      (node (ref "IC1") (pin "11") (pinfunction "O8_11") (pintype "open_collector"))
      (node (ref "X3") (pin "3") (pinfunction "SK_3") (pintype "passive"))
    )
    (net (code "57") (name "Net-(IC2-CD+)") (class "Default")
      (node (ref "IC2") (pin "10") (pinfunction "CD+_10") (pintype "passive"))
      (node (ref "X4") (pin "2") (pinfunction "SK_2") (pintype "passive"))
    )
    (net (code "58") (name "Net-(IC2-I1)") (class "Default")
      (node (ref "IC2") (pin "1") (pinfunction "I1_1") (pintype "input"))
      (node (ref "OK7") (pin "15") (pinfunction "EMIT_15") (pintype "passive"))
    )
    (net (code "59") (name "Net-(IC2-I2)") (class "Default")
      (node (ref "IC2") (pin "2") (pinfunction "I2_2") (pintype "input"))
      (node (ref "OK7") (pin "13") (pinfunction "EMIT_13") (pintype "passive"))
    )
    (net (code "60") (name "Net-(IC2-I3)") (class "Default")
      (node (ref "IC2") (pin "3") (pinfunction "I3_3") (pintype "input"))
      (node (ref "OK7") (pin "11") (pinfunction "EMIT_11") (pintype "passive"))
    )
    (net (code "61") (name "Net-(IC2-I4)") (class "Default")
      (node (ref "IC2") (pin "4") (pinfunction "I4_4") (pintype "input"))
      (node (ref "OK7") (pin "9") (pinfunction "EMIT_9") (pintype "passive"))
    )
    (net (code "62") (name "Net-(IC2-I5)") (class "Default")
      (node (ref "IC2") (pin "5") (pinfunction "I5_5") (pintype "input"))
      (node (ref "OK8") (pin "15") (pinfunction "EMIT_15") (pintype "passive"))
    )
    (net (code "63") (name "Net-(IC2-I6)") (class "Default")
      (node (ref "IC2") (pin "6") (pinfunction "I6_6") (pintype "input"))
      (node (ref "OK8") (pin "13") (pinfunction "EMIT_13") (pintype "passive"))
    )
    (net (code "64") (name "Net-(IC2-I7)") (class "Default")
      (node (ref "IC2") (pin "7") (pinfunction "I7_7") (pintype "input"))
      (node (ref "OK8") (pin "11") (pinfunction "EMIT_11") (pintype "passive"))
    )
    (net (code "65") (name "Net-(IC2-I8)") (class "Default")
      (node (ref "IC2") (pin "8") (pinfunction "I8_8") (pintype "input"))
      (node (ref "OK8") (pin "9") (pinfunction "EMIT_9") (pintype "passive"))
    )
    (net (code "66") (name "Net-(IC2-O1)") (class "Default")
      (node (ref "IC2") (pin "18") (pinfunction "O1_18") (pintype "open_collector"))
      (node (ref "X4") (pin "10") (pinfunction "SK_10") (pintype "passive"))
    )
    (net (code "67") (name "Net-(IC2-O2)") (class "Default")
      (node (ref "IC2") (pin "17") (pinfunction "O2_17") (pintype "open_collector"))
      (node (ref "X4") (pin "9") (pinfunction "SK_9") (pintype "passive"))
    )
    (net (code "68") (name "Net-(IC2-O3)") (class "Default")
      (node (ref "IC2") (pin "16") (pinfunction "O3_16") (pintype "open_collector"))
      (node (ref "X4") (pin "8") (pinfunction "SK_8") (pintype "passive"))
    )
    (net (code "69") (name "Net-(IC2-O4)") (class "Default")
      (node (ref "IC2") (pin "15") (pinfunction "O4_15") (pintype "open_collector"))
      (node (ref "X4") (pin "7") (pinfunction "SK_7") (pintype "passive"))
    )
    (net (code "70") (name "Net-(IC2-O5)") (class "Default")
      (node (ref "IC2") (pin "14") (pinfunction "O5_14") (pintype "open_collector"))
      (node (ref "X4") (pin "6") (pinfunction "SK_6") (pintype "passive"))
    )
    (net (code "71") (name "Net-(IC2-O6)") (class "Default")
      (node (ref "IC2") (pin "13") (pinfunction "O6_13") (pintype "open_collector"))
      (node (ref "X4") (pin "5") (pinfunction "SK_5") (pintype "passive"))
    )
    (net (code "72") (name "Net-(IC2-O7)") (class "Default")
      (node (ref "IC2") (pin "12") (pinfunction "O7_12") (pintype "open_collector"))
      (node (ref "X4") (pin "4") (pinfunction "SK_4") (pintype "passive"))
    )
    (net (code "73") (name "Net-(IC2-O8)") (class "Default")
      (node (ref "IC2") (pin "11") (pinfunction "O8_11") (pintype "open_collector"))
      (node (ref "X4") (pin "3") (pinfunction "SK_3") (pintype "passive"))
    )
    (net (code "74") (name "Net-(OK1A-A)") (class "Default")
      (node (ref "OK1") (pin "1") (pinfunction "A_1") (pintype "passive"))
      (node (ref "R1") (pin "1") (pinfunction "1_1") (pintype "passive"))
    )
    (net (code "75") (name "Net-(OK1A-C)") (class "Default")
      (node (ref "OK1") (pin "2") (pinfunction "C_2") (pintype "passive"))
      (node (ref "X1") (pin "2") (pinfunction "SK_2") (pintype "passive"))
    )
    (net (code "76") (name "Net-(OK1A-COL)") (class "Default")
      (node (ref "OK1") (pin "16") (pinfunction "COL_16") (pintype "passive"))
      (node (ref "R17") (pin "1") (pinfunction "1_1") (pintype "passive"))
    )
    (net (code "77") (name "Net-(OK1B-A)") (class "Default")
      (node (ref "OK1") (pin "3") (pinfunction "A_3") (pintype "passive"))
      (node (ref "R2") (pin "1") (pinfunction "1_1") (pintype "passive"))
    )
    (net (code "78") (name "Net-(OK1B-C)") (class "Default")
      (node (ref "OK1") (pin "4") (pinfunction "C_4") (pintype "passive"))
      (node (ref "X1") (pin "3") (pinfunction "SK_3") (pintype "passive"))
    )
    (net (code "79") (name "Net-(OK1B-COL)") (class "Default")
      (node (ref "OK1") (pin "14") (pinfunction "COL_14") (pintype "passive"))
      (node (ref "R18") (pin "1") (pinfunction "1_1") (pintype "passive"))
    )
    (net (code "80") (name "Net-(OK1C-A)") (class "Default")
      (node (ref "OK1") (pin "5") (pinfunction "A_5") (pintype "passive"))
      (node (ref "R3") (pin "1") (pinfunction "1_1") (pintype "passive"))
    )
    (net (code "81") (name "Net-(OK1C-C)") (class "Default")
      (node (ref "OK1") (pin "6") (pinfunction "C_6") (pintype "passive"))
      (node (ref "X1") (pin "4") (pinfunction "SK_4") (pintype "passive"))
    )
    (net (code "82") (name "Net-(OK1C-COL)") (class "Default")
      (node (ref "OK1") (pin "12") (pinfunction "COL_12") (pintype "passive"))
      (node (ref "R19") (pin "1") (pinfunction "1_1") (pintype "passive"))
    )
    (net (code "83") (name "Net-(OK1D-A)") (class "Default")
      (node (ref "OK1") (pin "7") (pinfunction "A_7") (pintype "passive"))
      (node (ref "R4") (pin "1") (pinfunction "1_1") (pintype "passive"))
    )
    (net (code "84") (name "Net-(OK1D-C)") (class "Default")
      (node (ref "OK1") (pin "8") (pinfunction "C_8") (pintype "passive"))
      (node (ref "X1") (pin "5") (pinfunction "SK_5") (pintype "passive"))
    )
    (net (code "85") (name "Net-(OK1D-COL)") (class "Default")
      (node (ref "OK1") (pin "10") (pinfunction "COL_10") (pintype "passive"))
      (node (ref "R20") (pin "1") (pinfunction "1_1") (pintype "passive"))
    )
    (net (code "86") (name "Net-(OK2A-A)") (class "Default")
      (node (ref "OK2") (pin "1") (pinfunction "A_1") (pintype "passive"))
      (node (ref "R5") (pin "1") (pinfunction "1_1") (pintype "passive"))
    )
    (net (code "87") (name "Net-(OK2A-C)") (class "Default")
      (node (ref "OK2") (pin "2") (pinfunction "C_2") (pintype "passive"))
      (node (ref "X1") (pin "6") (pinfunction "SK_6") (pintype "passive"))
    )
    (net (code "88") (name "Net-(OK2A-COL)") (class "Default")
      (node (ref "OK2") (pin "16") (pinfunction "COL_16") (pintype "passive"))
      (node (ref "R21") (pin "1") (pinfunction "1_1") (pintype "passive"))
    )
    (net (code "89") (name "Net-(OK2B-A)") (class "Default")
      (node (ref "OK2") (pin "3") (pinfunction "A_3") (pintype "passive"))
      (node (ref "R6") (pin "1") (pinfunction "1_1") (pintype "passive"))
    )
    (net (code "90") (name "Net-(OK2B-C)") (class "Default")
      (node (ref "OK2") (pin "4") (pinfunction "C_4") (pintype "passive"))
      (node (ref "X1") (pin "7") (pinfunction "SK_7") (pintype "passive"))
    )
    (net (code "91") (name "Net-(OK2B-COL)") (class "Default")
      (node (ref "OK2") (pin "14") (pinfunction "COL_14") (pintype "passive"))
      (node (ref "R22") (pin "1") (pinfunction "1_1") (pintype "passive"))
    )
    (net (code "92") (name "Net-(OK2C-A)") (class "Default")
      (node (ref "OK2") (pin "5") (pinfunction "A_5") (pintype "passive"))
      (node (ref "R7") (pin "1") (pinfunction "1_1") (pintype "passive"))
    )
    (net (code "93") (name "Net-(OK2C-C)") (class "Default")
      (node (ref "OK2") (pin "6") (pinfunction "C_6") (pintype "passive"))
      (node (ref "X1") (pin "8") (pinfunction "SK_8") (pintype "passive"))
    )
    (net (code "94") (name "Net-(OK2C-COL)") (class "Default")
      (node (ref "OK2") (pin "12") (pinfunction "COL_12") (pintype "passive"))
      (node (ref "R23") (pin "1") (pinfunction "1_1") (pintype "passive"))
    )
    (net (code "95") (name "Net-(OK2D-A)") (class "Default")
      (node (ref "OK2") (pin "7") (pinfunction "A_7") (pintype "passive"))
      (node (ref "R8") (pin "1") (pinfunction "1_1") (pintype "passive"))
    )
    (net (code "96") (name "Net-(OK2D-C)") (class "Default")
      (node (ref "OK2") (pin "8") (pinfunction "C_8") (pintype "passive"))
      (node (ref "X1") (pin "9") (pinfunction "SK_9") (pintype "passive"))
    )
    (net (code "97") (name "Net-(OK2D-COL)") (class "Default")
      (node (ref "OK2") (pin "10") (pinfunction "COL_10") (pintype "passive"))
      (node (ref "R24") (pin "1") (pinfunction "1_1") (pintype "passive"))
    )
    (net (code "98") (name "Net-(OK3A-A)") (class "Default")
      (node (ref "OK3") (pin "1") (pinfunction "A_1") (pintype "passive"))
      (node (ref "R9") (pin "1") (pinfunction "1_1") (pintype "passive"))
    )
    (net (code "99") (name "Net-(OK3A-C)") (class "Default")
      (node (ref "OK3") (pin "2") (pinfunction "C_2") (pintype "passive"))
      (node (ref "X2") (pin "2") (pinfunction "SK_2") (pintype "passive"))
    )
    (net (code "100") (name "Net-(OK3A-COL)") (class "Default")
      (node (ref "OK3") (pin "16") (pinfunction "COL_16") (pintype "passive"))
      (node (ref "R25") (pin "1") (pinfunction "1_1") (pintype "passive"))
    )
    (net (code "101") (name "Net-(OK3B-A)") (class "Default")
      (node (ref "OK3") (pin "3") (pinfunction "A_3") (pintype "passive"))
      (node (ref "R10") (pin "1") (pinfunction "1_1") (pintype "passive"))
    )
    (net (code "102") (name "Net-(OK3B-C)") (class "Default")
      (node (ref "OK3") (pin "4") (pinfunction "C_4") (pintype "passive"))
      (node (ref "X2") (pin "3") (pinfunction "SK_3") (pintype "passive"))
    )
    (net (code "103") (name "Net-(OK3B-COL)") (class "Default")
      (node (ref "OK3") (pin "14") (pinfunction "COL_14") (pintype "passive"))
      (node (ref "R26") (pin "1") (pinfunction "1_1") (pintype "passive"))
    )
    (net (code "104") (name "Net-(OK3C-A)") (class "Default")
      (node (ref "OK3") (pin "5") (pinfunction "A_5") (pintype "passive"))
      (node (ref "R11") (pin "1") (pinfunction "1_1") (pintype "passive"))
    )
    (net (code "105") (name "Net-(OK3C-C)") (class "Default")
      (node (ref "OK3") (pin "6") (pinfunction "C_6") (pintype "passive"))
      (node (ref "X2") (pin "4") (pinfunction "SK_4") (pintype "passive"))
    )
    (net (code "106") (name "Net-(OK3C-COL)") (class "Default")
      (node (ref "OK3") (pin "12") (pinfunction "COL_12") (pintype "passive"))
      (node (ref "R27") (pin "1") (pinfunction "1_1") (pintype "passive"))
    )
    (net (code "107") (name "Net-(OK3D-A)") (class "Default")
      (node (ref "OK3") (pin "7") (pinfunction "A_7") (pintype "passive"))
      (node (ref "R12") (pin "1") (pinfunction "1_1") (pintype "passive"))
    )
    (net (code "108") (name "Net-(OK3D-C)") (class "Default")
      (node (ref "OK3") (pin "8") (pinfunction "C_8") (pintype "passive"))
      (node (ref "X2") (pin "5") (pinfunction "SK_5") (pintype "passive"))
    )
    (net (code "109") (name "Net-(OK3D-COL)") (class "Default")
      (node (ref "OK3") (pin "10") (pinfunction "COL_10") (pintype "passive"))
      (node (ref "R28") (pin "1") (pinfunction "1_1") (pintype "passive"))
    )
    (net (code "110") (name "Net-(OK4A-A)") (class "Default")
      (node (ref "OK4") (pin "1") (pinfunction "A_1") (pintype "passive"))
      (node (ref "R13") (pin "1") (pinfunction "1_1") (pintype "passive"))
    )
    (net (code "111") (name "Net-(OK4A-C)") (class "Default")
      (node (ref "OK4") (pin "2") (pinfunction "C_2") (pintype "passive"))
      (node (ref "X2") (pin "6") (pinfunction "SK_6") (pintype "passive"))
    )
    (net (code "112") (name "Net-(OK4A-COL)") (class "Default")
      (node (ref "OK4") (pin "16") (pinfunction "COL_16") (pintype "passive"))
      (node (ref "R29") (pin "1") (pinfunction "1_1") (pintype "passive"))
    )
    (net (code "113") (name "Net-(OK4B-A)") (class "Default")
      (node (ref "OK4") (pin "3") (pinfunction "A_3") (pintype "passive"))
      (node (ref "R14") (pin "1") (pinfunction "1_1") (pintype "passive"))
    )
    (net (code "114") (name "Net-(OK4B-C)") (class "Default")
      (node (ref "OK4") (pin "4") (pinfunction "C_4") (pintype "passive"))
      (node (ref "X2") (pin "7") (pinfunction "SK_7") (pintype "passive"))
    )
    (net (code "115") (name "Net-(OK4B-COL)") (class "Default")
      (node (ref "OK4") (pin "14") (pinfunction "COL_14") (pintype "passive"))
      (node (ref "R30") (pin "1") (pinfunction "1_1") (pintype "passive"))
    )
    (net (code "116") (name "Net-(OK4C-A)") (class "Default")
      (node (ref "OK4") (pin "5") (pinfunction "A_5") (pintype "passive"))
      (node (ref "R15") (pin "1") (pinfunction "1_1") (pintype "passive"))
    )
    (net (code "117") (name "Net-(OK4C-C)") (class "Default")
      (node (ref "OK4") (pin "6") (pinfunction "C_6") (pintype "passive"))
      (node (ref "X2") (pin "8") (pinfunction "SK_8") (pintype "passive"))
    )
    (net (code "118") (name "Net-(OK4C-COL)") (class "Default")
      (node (ref "OK4") (pin "12") (pinfunction "COL_12") (pintype "passive"))
      (node (ref "R31") (pin "1") (pinfunction "1_1") (pintype "passive"))
    )
    (net (code "119") (name "Net-(OK4D-A)") (class "Default")
      (node (ref "OK4") (pin "7") (pinfunction "A_7") (pintype "passive"))
      (node (ref "R16") (pin "1") (pinfunction "1_1") (pintype "passive"))
    )
    (net (code "120") (name "Net-(OK4D-C)") (class "Default")
      (node (ref "OK4") (pin "8") (pinfunction "C_8") (pintype "passive"))
      (node (ref "X2") (pin "9") (pinfunction "SK_9") (pintype "passive"))
    )
    (net (code "121") (name "Net-(OK4D-COL)") (class "Default")
      (node (ref "OK4") (pin "10") (pinfunction "COL_10") (pintype "passive"))
      (node (ref "R32") (pin "1") (pinfunction "1_1") (pintype "passive"))
    )
    (net (code "122") (name "Net-(OK5A-C)") (class "Default")
      (node (ref "OK5") (pin "2") (pinfunction "C_2") (pintype "passive"))
      (node (ref "R33") (pin "2") (pinfunction "2_2") (pintype "passive"))
    )
    (net (code "123") (name "Net-(OK5A-COL)") (class "Default")
      (node (ref "OK5") (pin "16") (pinfunction "COL_16") (pintype "passive"))
      (node (ref "R49") (pin "1") (pinfunction "1_1") (pintype "passive"))
    )
    (net (code "124") (name "Net-(OK5B-C)") (class "Default")
      (node (ref "OK5") (pin "4") (pinfunction "C_4") (pintype "passive"))
      (node (ref "R34") (pin "2") (pinfunction "2_2") (pintype "passive"))
    )
    (net (code "125") (name "Net-(OK5B-COL)") (class "Default")
      (node (ref "OK5") (pin "14") (pinfunction "COL_14") (pintype "passive"))
      (node (ref "R50") (pin "1") (pinfunction "1_1") (pintype "passive"))
    )
    (net (code "126") (name "Net-(OK5C-C)") (class "Default")
      (node (ref "OK5") (pin "6") (pinfunction "C_6") (pintype "passive"))
      (node (ref "R35") (pin "2") (pinfunction "2_2") (pintype "passive"))
    )
    (net (code "127") (name "Net-(OK5C-COL)") (class "Default")
      (node (ref "OK5") (pin "12") (pinfunction "COL_12") (pintype "passive"))
      (node (ref "R51") (pin "1") (pinfunction "1_1") (pintype "passive"))
    )
    (net (code "128") (name "Net-(OK5D-C)") (class "Default")
      (node (ref "OK5") (pin "8") (pinfunction "C_8") (pintype "passive"))
      (node (ref "R36") (pin "2") (pinfunction "2_2") (pintype "passive"))
    )
    (net (code "129") (name "Net-(OK5D-COL)") (class "Default")
      (node (ref "OK5") (pin "10") (pinfunction "COL_10") (pintype "passive"))
      (node (ref "R52") (pin "1") (pinfunction "1_1") (pintype "passive"))
    )
    (net (code "130") (name "Net-(OK6A-C)") (class "Default")
      (node (ref "OK6") (pin "2") (pinfunction "C_2") (pintype "passive"))
      (node (ref "R37") (pin "2") (pinfunction "2_2") (pintype "passive"))
    )
    (net (code "131") (name "Net-(OK6A-COL)") (class "Default")
      (node (ref "OK6") (pin "16") (pinfunction "COL_16") (pintype "passive"))
      (node (ref "R53") (pin "1") (pinfunction "1_1") (pintype "passive"))
    )
    (net (code "132") (name "Net-(OK6B-C)") (class "Default")
      (node (ref "OK6") (pin "4") (pinfunction "C_4") (pintype "passive"))
      (node (ref "R38") (pin "2") (pinfunction "2_2") (pintype "passive"))
    )
    (net (code "133") (name "Net-(OK6B-COL)") (class "Default")
      (node (ref "OK6") (pin "14") (pinfunction "COL_14") (pintype "passive"))
      (node (ref "R54") (pin "1") (pinfunction "1_1") (pintype "passive"))
    )
    (net (code "134") (name "Net-(OK6C-C)") (class "Default")
      (node (ref "OK6") (pin "6") (pinfunction "C_6") (pintype "passive"))
      (node (ref "R39") (pin "2") (pinfunction "2_2") (pintype "passive"))
    )
    (net (code "135") (name "Net-(OK6C-COL)") (class "Default")
      (node (ref "OK6") (pin "12") (pinfunction "COL_12") (pintype "passive"))
      (node (ref "R55") (pin "1") (pinfunction "1_1") (pintype "passive"))
    )
    (net (code "136") (name "Net-(OK6D-C)") (class "Default")
      (node (ref "OK6") (pin "8") (pinfunction "C_8") (pintype "passive"))
      (node (ref "R40") (pin "2") (pinfunction "2_2") (pintype "passive"))
    )
    (net (code "137") (name "Net-(OK6D-COL)") (class "Default")
      (node (ref "OK6") (pin "10") (pinfunction "COL_10") (pintype "passive"))
      (node (ref "R56") (pin "1") (pinfunction "1_1") (pintype "passive"))
    )
    (net (code "138") (name "Net-(OK7A-C)") (class "Default")
      (node (ref "OK7") (pin "2") (pinfunction "C_2") (pintype "passive"))
      (node (ref "R41") (pin "2") (pinfunction "2_2") (pintype "passive"))
    )
    (net (code "139") (name "Net-(OK7A-COL)") (class "Default")
      (node (ref "OK7") (pin "16") (pinfunction "COL_16") (pintype "passive"))
      (node (ref "R57") (pin "1") (pinfunction "1_1") (pintype "passive"))
    )
    (net (code "140") (name "Net-(OK7B-C)") (class "Default")
      (node (ref "OK7") (pin "4") (pinfunction "C_4") (pintype "passive"))
      (node (ref "R42") (pin "2") (pinfunction "2_2") (pintype "passive"))
    )
    (net (code "141") (name "Net-(OK7B-COL)") (class "Default")
      (node (ref "OK7") (pin "14") (pinfunction "COL_14") (pintype "passive"))
      (node (ref "R58") (pin "1") (pinfunction "1_1") (pintype "passive"))
    )
    (net (code "142") (name "Net-(OK7C-C)") (class "Default")
      (node (ref "OK7") (pin "6") (pinfunction "C_6") (pintype "passive"))
      (node (ref "R43") (pin "2") (pinfunction "2_2") (pintype "passive"))
    )
    (net (code "143") (name "Net-(OK7C-COL)") (class "Default")
      (node (ref "OK7") (pin "12") (pinfunction "COL_12") (pintype "passive"))
      (node (ref "R59") (pin "1") (pinfunction "1_1") (pintype "passive"))
    )
    (net (code "144") (name "Net-(OK7D-C)") (class "Default")
      (node (ref "OK7") (pin "8") (pinfunction "C_8") (pintype "passive"))
      (node (ref "R44") (pin "2") (pinfunction "2_2") (pintype "passive"))
    )
    (net (code "145") (name "Net-(OK7D-COL)") (class "Default")
      (node (ref "OK7") (pin "10") (pinfunction "COL_10") (pintype "passive"))
      (node (ref "R60") (pin "1") (pinfunction "1_1") (pintype "passive"))
    )
    (net (code "146") (name "Net-(OK8A-C)") (class "Default")
      (node (ref "OK8") (pin "2") (pinfunction "C_2") (pintype "passive"))
      (node (ref "R45") (pin "2") (pinfunction "2_2") (pintype "passive"))
    )
    (net (code "147") (name "Net-(OK8A-COL)") (class "Default")
      (node (ref "OK8") (pin "16") (pinfunction "COL_16") (pintype "passive"))
      (node (ref "R61") (pin "1") (pinfunction "1_1") (pintype "passive"))
    )
    (net (code "148") (name "Net-(OK8B-C)") (class "Default")
      (node (ref "OK8") (pin "4") (pinfunction "C_4") (pintype "passive"))
      (node (ref "R46") (pin "2") (pinfunction "2_2") (pintype "passive"))
    )
    (net (code "149") (name "Net-(OK8B-COL)") (class "Default")
      (node (ref "OK8") (pin "14") (pinfunction "COL_14") (pintype "passive"))
      (node (ref "R62") (pin "1") (pinfunction "1_1") (pintype "passive"))
    )
    (net (code "150") (name "Net-(OK8C-C)") (class "Default")
      (node (ref "OK8") (pin "6") (pinfunction "C_6") (pintype "passive"))
      (node (ref "R47") (pin "2") (pinfunction "2_2") (pintype "passive"))
    )
    (net (code "151") (name "Net-(OK8C-COL)") (class "Default")
      (node (ref "OK8") (pin "12") (pinfunction "COL_12") (pintype "passive"))
      (node (ref "R63") (pin "1") (pinfunction "1_1") (pintype "passive"))
    )
    (net (code "152") (name "Net-(OK8D-C)") (class "Default")
      (node (ref "OK8") (pin "8") (pinfunction "C_8") (pintype "passive"))
      (node (ref "R48") (pin "2") (pinfunction "2_2") (pintype "passive"))
    )
    (net (code "153") (name "Net-(OK8D-COL)") (class "Default")
      (node (ref "OK8") (pin "10") (pinfunction "COL_10") (pintype "passive"))
      (node (ref "R64") (pin "1") (pinfunction "1_1") (pintype "passive"))
    )
    (net (code "154") (name "Net-(U$2-I2C2_SCL)") (class "Default")
      (node (ref "R65") (pin "1") (pinfunction "1_1") (pintype "passive"))
      (node (ref "U$2") (pin "65") (pinfunction "I2C2_SCL_65") (pintype "bidirectional"))
      (node (ref "U$52") (pin "16") (pinfunction "SCL_16") (pintype "input"))
      (node (ref "U1") (pin "6") (pinfunction "SCL_6") (pintype "input"))
    )
    (net (code "155") (name "Net-(U$2-I2C2_SDA)") (class "Default")
      (node (ref "R66") (pin "1") (pinfunction "1_1") (pintype "passive"))
      (node (ref "U$2") (pin "66") (pinfunction "I2C2_SDA_66") (pintype "bidirectional"))
      (node (ref "U$52") (pin "15") (pinfunction "SDA_15") (pintype "input"))
      (node (ref "U1") (pin "5") (pinfunction "SDA_5") (pintype "bidirectional"))
    )
    (net (code "156") (name "Net-(U$52-CLR)") (class "Default")
      (node (ref "R72") (pin "1") (pinfunction "1_1") (pintype "passive"))
      (node (ref "U$52") (pin "9") (pinfunction "CLR_9") (pintype "input"))
    )
    (net (code "157") (name "Net-(U$52-VOUTB)") (class "Default")
      (node (ref "U$52") (pin "13") (pinfunction "VOUTB_13") (pintype "output"))
      (node (ref "X8") (pin "4") (pinfunction "SK_4") (pintype "passive"))
    )
    (net (code "158") (name "Net-(U$52-VOUTD)") (class "Default")
      (node (ref "U$52") (pin "12") (pinfunction "VOUTD_12") (pintype "output"))
      (node (ref "X8") (pin "2") (pinfunction "SK_2") (pintype "passive"))
    )
    (net (code "159") (name "Net-(U$53-A)") (class "Default")
      (node (ref "U$53") (pin "12") (pinfunction "A_12") (pintype "passive"))
      (node (ref "X5") (pin "1") (pinfunction "M_1") (pintype "passive"))
    )
    (net (code "160") (name "Net-(U$53-B)") (class "Default")
      (node (ref "U$53") (pin "11") (pinfunction "B_11") (pintype "passive"))
      (node (ref "X5") (pin "2") (pinfunction "M_2") (pintype "passive"))
    )
    (net (code "161") (name "Net-(U$53-H{slash}F)") (class "Default")
      (node (ref "JP1") (pin "1") (pinfunction "1_1") (pintype "passive"))
      (node (ref "U$53") (pin "1") (pinfunction "H/F_1") (pintype "input"))
    )
    (net (code "162") (name "Net-(U$53-RXP)") (class "Default")
      (node (ref "JP7") (pin "2") (pinfunction "2_2") (pintype "passive"))
      (node (ref "U$53") (pin "13") (pinfunction "RXP_13") (pintype "input"))
    )
    (net (code "163") (name "Net-(U$53-SRL)") (class "Default")
      (node (ref "JP2") (pin "2") (pinfunction "2_2") (pintype "passive"))
      (node (ref "U$53") (pin "6") (pinfunction "SRL_6") (pintype "input"))
    )
    (net (code "164") (name "Net-(U$53-TXP)") (class "Default")
      (node (ref "JP6") (pin "2") (pinfunction "2_2") (pintype "passive"))
      (node (ref "U$53") (pin "8") (pinfunction "TXP_8") (pintype "input"))
    )
    (net (code "165") (name "Net-(U$53-Y)") (class "Default")
      (node (ref "U$53") (pin "9") (pinfunction "Y_9") (pintype "passive"))
      (node (ref "X5") (pin "4") (pinfunction "M_4") (pintype "passive"))
    )
    (net (code "166") (name "Net-(U$53-Z)") (class "Default")
      (node (ref "U$53") (pin "10") (pinfunction "Z_10") (pintype "passive"))
      (node (ref "X5") (pin "3") (pinfunction "M_3") (pintype "passive"))
    )
    (net (code "167") (name "Net-(U$54-A)") (class "Default")
      (node (ref "U$54") (pin "12") (pinfunction "A_12") (pintype "passive"))
      (node (ref "X6") (pin "1") (pinfunction "M_1") (pintype "passive"))
    )
    (net (code "168") (name "Net-(U$54-B)") (class "Default")
      (node (ref "U$54") (pin "11") (pinfunction "B_11") (pintype "passive"))
      (node (ref "X6") (pin "2") (pinfunction "M_2") (pintype "passive"))
    )
    (net (code "169") (name "Net-(U$54-H{slash}F)") (class "Default")
      (node (ref "JP4") (pin "1") (pinfunction "1_1") (pintype "passive"))
      (node (ref "U$54") (pin "1") (pinfunction "H/F_1") (pintype "input"))
    )
    (net (code "170") (name "Net-(U$54-RXP)") (class "Default")
      (node (ref "JP8") (pin "2") (pinfunction "2_2") (pintype "passive"))
      (node (ref "U$54") (pin "13") (pinfunction "RXP_13") (pintype "input"))
    )
    (net (code "171") (name "Net-(U$54-SRL)") (class "Default")
      (node (ref "JP3") (pin "2") (pinfunction "2_2") (pintype "passive"))
      (node (ref "U$54") (pin "6") (pinfunction "SRL_6") (pintype "input"))
    )
    (net (code "172") (name "Net-(U$54-TXP)") (class "Default")
      (node (ref "JP5") (pin "2") (pinfunction "2_2") (pintype "passive"))
      (node (ref "U$54") (pin "8") (pinfunction "TXP_8") (pintype "input"))
    )
    (net (code "173") (name "Net-(U$54-Y)") (class "Default")
      (node (ref "U$54") (pin "9") (pinfunction "Y_9") (pintype "passive"))
      (node (ref "X6") (pin "4") (pinfunction "M_4") (pintype "passive"))
    )
    (net (code "174") (name "Net-(U$54-Z)") (class "Default")
      (node (ref "U$54") (pin "10") (pinfunction "Z_10") (pintype "passive"))
      (node (ref "X6") (pin "3") (pinfunction "M_3") (pintype "passive"))
    )
    (net (code "175") (name "Net-(U1-A0)") (class "Default")
      (node (ref "R69") (pin "1") (pinfunction "1_1") (pintype "passive"))
      (node (ref "S1") (pin "4") (pinfunction "4_4") (pintype "passive"))
      (node (ref "U1") (pin "1") (pinfunction "A0_1") (pintype "input"))
    )
    (net (code "176") (name "Net-(U1-A1)") (class "Default")
      (node (ref "R68") (pin "1") (pinfunction "1_1") (pintype "passive"))
      (node (ref "S1") (pin "3") (pinfunction "3_3") (pintype "passive"))
      (node (ref "U1") (pin "2") (pinfunction "A1_2") (pintype "input"))
    )
    (net (code "177") (name "Net-(U1-A2)") (class "Default")
      (node (ref "R67") (pin "1") (pinfunction "1_1") (pintype "passive"))
      (node (ref "U1") (pin "3") (pinfunction "A2_3") (pintype "input"))
    )
    (net (code "178") (name "Net-(U1-WP)") (class "Default")
      (node (ref "R70") (pin "1") (pinfunction "1_1") (pintype "passive"))
      (node (ref "R71") (pin "1") (pinfunction "1_1") (pintype "passive"))
      (node (ref "U1") (pin "7") (pinfunction "WP_7") (pintype "input"))
    )
    (net (code "179") (name "Net-(X7A-SK)") (class "Default")
      (node (ref "D1") (pin "A") (pinfunction "A_A") (pintype "passive"))
      (node (ref "X7") (pin "1") (pinfunction "SK_1") (pintype "passive"))
    )
    (net (code "180") (name "RAW_5V") (class "Default")
      (node (ref "IC3") (pin "3") (pinfunction "VO_3") (pintype "passive"))
      (node (ref "U$2") (pin "51") (pinfunction "VDD_5V_51") (pintype "power_in"))
      (node (ref "U$2") (pin "52") (pinfunction "VDD_5V_52") (pintype "power_in"))
    )
    (net (code "181") (name "RS422_RX") (class "Default")
      (node (ref "U$2") (pin "68") (pinfunction "UART2_RXD_68") (pintype "input"))
      (node (ref "U$53") (pin "2") (pinfunction "RO_2") (pintype "output"))
    )
    (net (code "182") (name "RS422_TX") (class "Default")
      (node (ref "U$2") (pin "67") (pinfunction "UART2_TXD_67") (pintype "output"))
      (node (ref "U$53") (pin "5") (pinfunction "DI_5") (pintype "input"))
    )
    (net (code "183") (name "RS485_RX") (class "Default")
      (node (ref "U$2") (pin "72") (pinfunction "UART1_RXD_72") (pintype "input"))
      (node (ref "U$54") (pin "2") (pinfunction "RO_2") (pintype "output"))
    )
    (net (code "184") (name "RS485_TX") (class "Default")
      (node (ref "U$2") (pin "70") (pinfunction "UART1_TXD_70") (pintype "output"))
      (node (ref "U$54") (pin "5") (pinfunction "DI_5") (pintype "input"))
    )
    (net (code "185") (name "VDD_ADC") (class "Default")
      (node (ref "U$2") (pin "78") (pinfunction "VDD_ADC_78") (pintype "power_in"))
    )
    (net (code "186") (name "unconnected-(U$2-AIN0-Pad85)") (class "Default")
      (node (ref "U$2") (pin "85") (pinfunction "AIN0_85") (pintype "input"))
    )
    (net (code "187") (name "unconnected-(U$2-AIN1-Pad86)") (class "Default")
      (node (ref "U$2") (pin "86") (pinfunction "AIN1_86") (pintype "input"))
    )
    (net (code "188") (name "unconnected-(U$2-AIN2-Pad83)") (class "Default")
      (node (ref "U$2") (pin "83") (pinfunction "AIN2_83") (pintype "input"))
    )
    (net (code "189") (name "unconnected-(U$2-AIN3-Pad84)") (class "Default")
      (node (ref "U$2") (pin "84") (pinfunction "AIN3_84") (pintype "input"))
    )
    (net (code "190") (name "unconnected-(U$2-AIN4-Pad79)") (class "Default")
      (node (ref "U$2") (pin "79") (pinfunction "AIN4_79") (pintype "input"))
    )
    (net (code "191") (name "unconnected-(U$2-AIN5-Pad82)") (class "Default")
      (node (ref "U$2") (pin "82") (pinfunction "AIN5_82") (pintype "input"))
    )
    (net (code "192") (name "unconnected-(U$2-AIN6-Pad81)") (class "Default")
      (node (ref "U$2") (pin "81") (pinfunction "AIN6_81") (pintype "input"))
    )
    (net (code "193") (name "unconnected-(U$2-EHRPWM2A-Pad19)") (class "Default")
      (node (ref "U$2") (pin "19") (pinfunction "EHRPWM2A_19") (pintype "bidirectional"))
    )
    (net (code "194") (name "unconnected-(U$2-EHRPWM2B-Pad13)") (class "Default")
      (node (ref "U$2") (pin "13") (pinfunction "EHRPWM2B_13") (pintype "bidirectional"))
    )
    (net (code "195") (name "unconnected-(U$2-GPIO0_26-Pad14)") (class "Default")
      (node (ref "U$2") (pin "14") (pinfunction "GPIO0_26_14") (pintype "bidirectional"))
    )
    (net (code "196") (name "unconnected-(U$2-GPIO0_27-Pad17)") (class "Default")
      (node (ref "U$2") (pin "17") (pinfunction "GPIO0_27_17") (pintype "bidirectional"))
    )
    (net (code "197") (name "unconnected-(U$2-GPIO1_12-Pad12)") (class "Default")
      (node (ref "U$2") (pin "12") (pinfunction "GPIO1_12_12") (pintype "bidirectional"))
    )
    (net (code "198") (name "unconnected-(U$2-GPIO1_13-Pad11)") (class "Default")
      (node (ref "U$2") (pin "11") (pinfunction "GPIO1_13_11") (pintype "bidirectional"))
    )
    (net (code "199") (name "unconnected-(U$2-GPIO1_14-Pad16)") (class "Default")
      (node (ref "U$2") (pin "16") (pinfunction "GPIO1_14_16") (pintype "bidirectional"))
    )
    (net (code "200") (name "unconnected-(U$2-GPIO1_15-Pad15)") (class "Default")
      (node (ref "U$2") (pin "15") (pinfunction "GPIO1_15_15") (pintype "bidirectional"))
    )
    (net (code "201") (name "unconnected-(U$2-GPIO1_30-Pad21)") (class "Default")
      (node (ref "U$2") (pin "21") (pinfunction "GPIO1_30_21") (pintype "bidirectional"))
    )
    (net (code "202") (name "unconnected-(U$2-GPIO1_31-Pad20)") (class "Default")
      (node (ref "U$2") (pin "20") (pinfunction "GPIO1_31_20") (pintype "bidirectional"))
    )
    (net (code "203") (name "unconnected-(U$2-GPIO2_6-Pad45)") (class "Default")
      (node (ref "U$2") (pin "45") (pinfunction "GPIO2_6_45") (pintype "bidirectional"))
    )
    (net (code "204") (name "unconnected-(U$2-GPIO2_7-Pad46)") (class "Default")
      (node (ref "U$2") (pin "46") (pinfunction "GPIO2_7_46") (pintype "bidirectional"))
    )
    (net (code "205") (name "unconnected-(U$2-GPIO2_8-Pad43)") (class "Default")
      (node (ref "U$2") (pin "43") (pinfunction "GPIO2_8_43") (pintype "bidirectional"))
    )
    (net (code "206") (name "unconnected-(U$2-GPIO2_9-Pad44)") (class "Default")
      (node (ref "U$2") (pin "44") (pinfunction "GPIO2_9_44") (pintype "bidirectional"))
    )
    (net (code "207") (name "unconnected-(U$2-GPIO2_10-Pad41)") (class "Default")
      (node (ref "U$2") (pin "41") (pinfunction "GPIO2_10_41") (pintype "bidirectional"))
    )
    (net (code "208") (name "unconnected-(U$2-GPIO2_11-Pad42)") (class "Default")
      (node (ref "U$2") (pin "42") (pinfunction "GPIO2_11_42") (pintype "bidirectional"))
    )
    (net (code "209") (name "unconnected-(U$2-GPIO2_12-Pad39)") (class "Default")
      (node (ref "U$2") (pin "39") (pinfunction "GPIO2_12_39") (pintype "bidirectional"))
    )
    (net (code "210") (name "unconnected-(U$2-GPIO2_13-Pad40)") (class "Default")
      (node (ref "U$2") (pin "40") (pinfunction "GPIO2_13_40") (pintype "bidirectional"))
    )
    (net (code "211") (name "unconnected-(U$2-GPIO2_22-Pad27)") (class "Default")
      (node (ref "U$2") (pin "27") (pinfunction "GPIO2_22_27") (pintype "bidirectional"))
    )
    (net (code "212") (name "unconnected-(U$2-GPIO2_23-Pad29)") (class "Default")
      (node (ref "U$2") (pin "29") (pinfunction "GPIO2_23_29") (pintype "bidirectional"))
    )
    (net (code "213") (name "unconnected-(U$2-GPIO2_24-Pad28)") (class "Default")
      (node (ref "U$2") (pin "28") (pinfunction "GPIO2_24_28") (pintype "bidirectional"))
    )
    (net (code "214") (name "unconnected-(U$2-GPIO2_25-Pad30)") (class "Default")
      (node (ref "U$2") (pin "30") (pinfunction "GPIO2_25_30") (pintype "bidirectional"))
    )
    (net (code "215") (name "unconnected-(U$2-PWR_BUT-Pad55)") (class "Default")
      (node (ref "U$2") (pin "55") (pinfunction "PWR_BUT_55") (pintype "bidirectional"))
    )
    (net (code "216") (name "unconnected-(U$2-SYS_RESETN-Pad56)") (class "Default")
      (node (ref "U$2") (pin "56") (pinfunction "SYS_RESETN_56") (pintype "input"))
    )
    (net (code "217") (name "unconnected-(U$2-UART3_CTSN-Pad36)") (class "Default")
      (node (ref "U$2") (pin "36") (pinfunction "UART3_CTSN_36") (pintype "bidirectional"))
    )
    (net (code "218") (name "unconnected-(U$2-UART3_RTSN-Pad34)") (class "Default")
      (node (ref "U$2") (pin "34") (pinfunction "UART3_RTSN_34") (pintype "bidirectional"))
    )
    (net (code "219") (name "unconnected-(U$2-UART4_CTSN-Pad35)") (class "Default")
      (node (ref "U$2") (pin "35") (pinfunction "UART4_CTSN_35") (pintype "bidirectional"))
    )
    (net (code "220") (name "unconnected-(U$2-UART4_RTSN-Pad33)") (class "Default")
      (node (ref "U$2") (pin "33") (pinfunction "UART4_RTSN_33") (pintype "bidirectional"))
    )
    (net (code "221") (name "unconnected-(U$2-UART5_CTSN-Pad31)") (class "Default")
      (node (ref "U$2") (pin "31") (pinfunction "UART5_CTSN_31") (pintype "bidirectional"))
    )
    (net (code "222") (name "unconnected-(U$2-UART5_RTSN-Pad32)") (class "Default")
      (node (ref "U$2") (pin "32") (pinfunction "UART5_RTSN_32") (pintype "bidirectional"))
    )
    (net (code "223") (name "unconnected-(U$2-UART5_RXD-Pad38)") (class "Default")
      (node (ref "U$2") (pin "38") (pinfunction "UART5_RXD_38") (pintype "input"))
    )
    (net (code "224") (name "unconnected-(U$2-UART5_TXD-Pad37)") (class "Default")
      (node (ref "U$2") (pin "37") (pinfunction "UART5_TXD_37") (pintype "output"))
    )
    (net (code "225") (name "unconnected-(U$52-LDAC-Pad1)") (class "Default")
      (node (ref "U$52") (pin "1") (pinfunction "LDAC_1") (pintype "passive"))
    )
    (net (code "226") (name "unconnected-(U$52-VOUTA-Pad4)") (class "Default")
      (node (ref "U$52") (pin "4") (pinfunction "VOUTA_4") (pintype "output"))
    )
    (net (code "227") (name "unconnected-(U$52-VOUTC-Pad5)") (class "Default")
      (node (ref "U$52") (pin "5") (pinfunction "VOUTC_5") (pintype "output"))
    )
    (net (code "228") (name "unconnected-(U$52-VOUTE-Pad6)") (class "Default")
      (node (ref "U$52") (pin "6") (pinfunction "VOUTE_6") (pintype "output"))
    )
    (net (code "229") (name "unconnected-(U$52-VOUTF-Pad11)") (class "Default")
      (node (ref "U$52") (pin "11") (pinfunction "VOUTF_11") (pintype "output"))
    )
    (net (code "230") (name "unconnected-(U$52-VOUTG-Pad7)") (class "Default")
      (node (ref "U$52") (pin "7") (pinfunction "VOUTG_7") (pintype "output"))
    )
    (net (code "231") (name "unconnected-(U$52-VOUTH-Pad10)") (class "Default")
      (node (ref "U$52") (pin "10") (pinfunction "VOUTH_10") (pintype "output"))
    )
    (net (code "232") (name "unconnected-(X5F-M-Pad6)") (class "Default")
      (node (ref "X5") (pin "6") (pinfunction "M_6") (pintype "passive"))
    )
    (net (code "233") (name "unconnected-(X5G-M-Pad7)") (class "Default")
      (node (ref "X5") (pin "7") (pinfunction "M_7") (pintype "passive"))
    )
    (net (code "234") (name "unconnected-(X5H-M-Pad8)") (class "Default")
      (node (ref "X5") (pin "8") (pinfunction "M_8") (pintype "passive"))
    )
    (net (code "235") (name "unconnected-(X5I-M-Pad9)") (class "Default")
      (node (ref "X5") (pin "9") (pinfunction "M_9") (pintype "passive"))
    )
    (net (code "236") (name "unconnected-(X6F-M-Pad6)") (class "Default")
      (node (ref "X6") (pin "6") (pinfunction "M_6") (pintype "passive"))
    )
    (net (code "237") (name "unconnected-(X6G-M-Pad7)") (class "Default")
      (node (ref "X6") (pin "7") (pinfunction "M_7") (pintype "passive"))
    )
    (net (code "238") (name "unconnected-(X6H-M-Pad8)") (class "Default")
      (node (ref "X6") (pin "8") (pinfunction "M_8") (pintype "passive"))
    )
    (net (code "239") (name "unconnected-(X6I-M-Pad9)") (class "Default")
      (node (ref "X6") (pin "9") (pinfunction "M_9") (pintype "passive"))
    )
  )
)
